# SignalRouting.net
KiCad netlist of a schematic drawn in Altium Designer
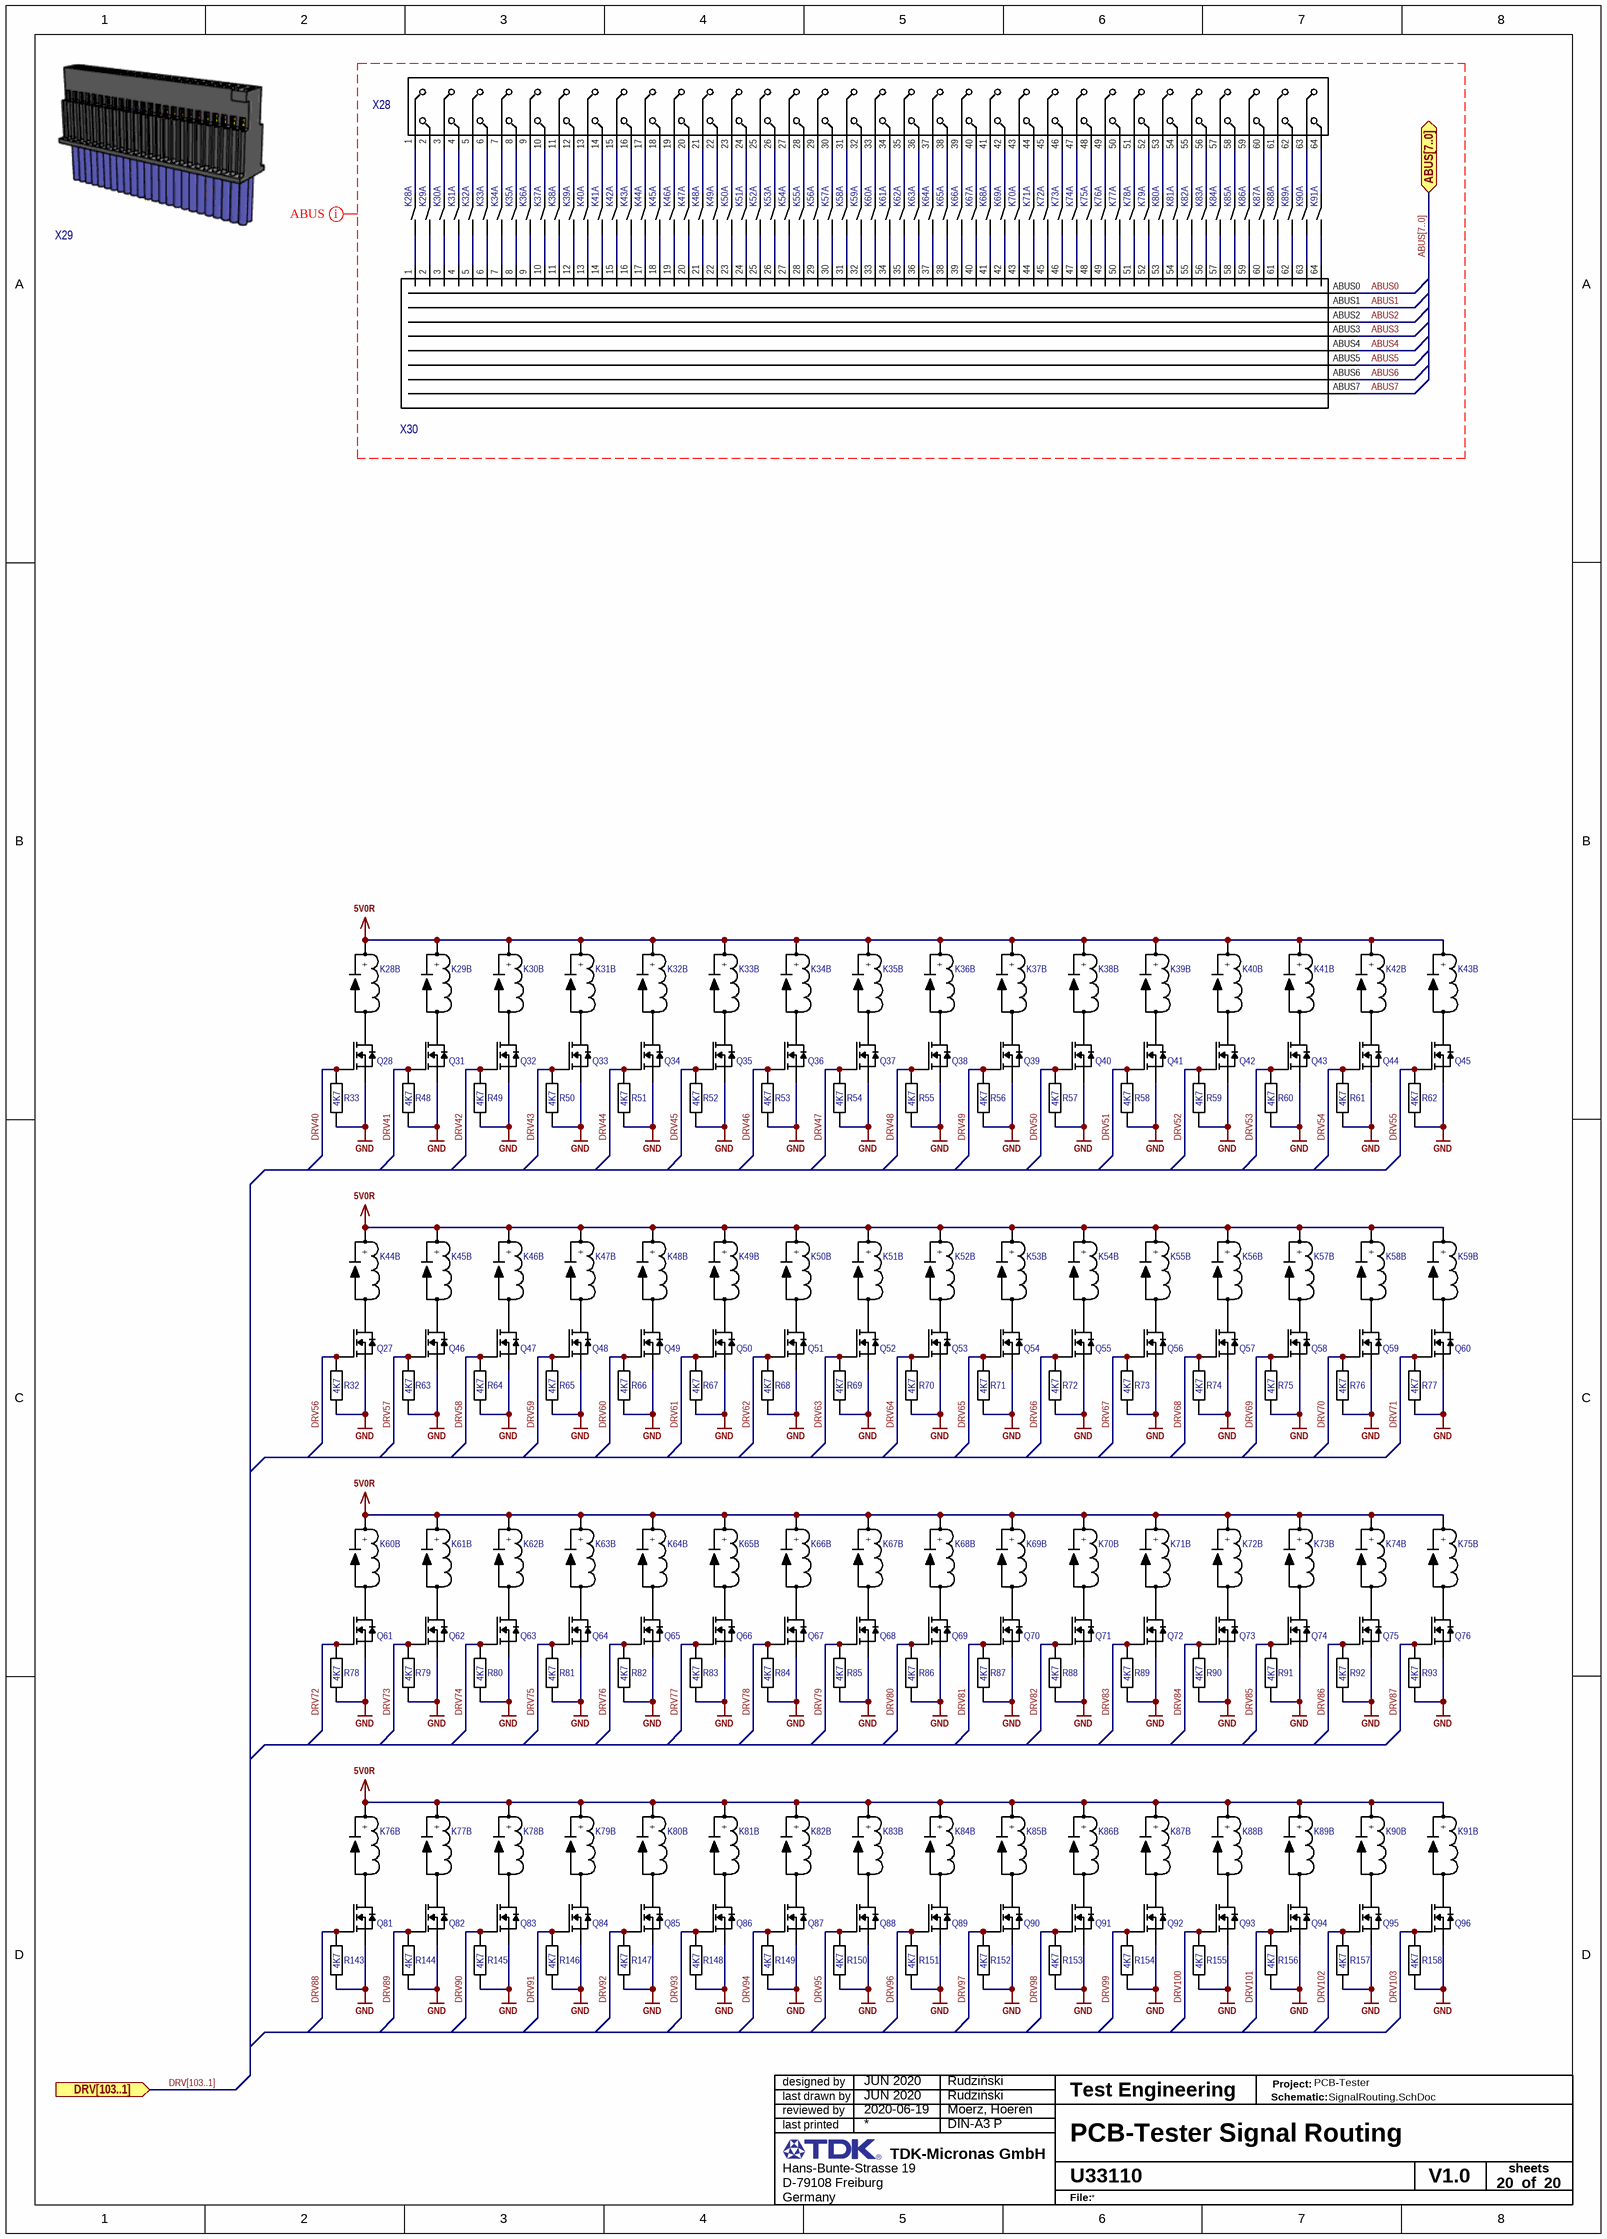
[diagram p0: SignalRouting.SchDoc]

(export (version "E")
  (design (tool "Eeschema 10.0.6"))
  (components
    (comp (ref "K28")
      (value "K")
      (footprint "118-1A")
      (description "5V Signal Relais, Normal Open")
      (fields
        (field (name "02. DISTRIBUTOR PART NUMBER") "118-1-A-5/2D")
        (field (name "13. CREATED DATE/NAME") "20.12.17 S. Kaiser")
      )
      (libsource (lib "chickenfood") (part "118-1-A-5/2D"))
    )
    (comp (ref "K29")
      (value "K")
      (footprint "118-1A")
      (description "5V Signal Relais, Normal Open")
      (fields
        (field (name "02. DISTRIBUTOR PART NUMBER") "118-1-A-5/2D")
        (field (name "13. CREATED DATE/NAME") "20.12.17 S. Kaiser")
      )
      (libsource (lib "") (part "118-1-A-5/2D_1"))
    )
    (comp (ref "K30")
      (value "K")
      (footprint "118-1A")
      (description "5V Signal Relais, Normal Open")
      (fields
        (field (name "02. DISTRIBUTOR PART NUMBER") "118-1-A-5/2D")
        (field (name "13. CREATED DATE/NAME") "20.12.17 S. Kaiser")
      )
      (libsource (lib "") (part "118-1-A-5/2D_1"))
    )
    (comp (ref "K31")
      (value "K")
      (footprint "118-1A")
      (description "5V Signal Relais, Normal Open")
      (fields
        (field (name "02. DISTRIBUTOR PART NUMBER") "118-1-A-5/2D")
        (field (name "13. CREATED DATE/NAME") "20.12.17 S. Kaiser")
      )
      (libsource (lib "chickenfood") (part "118-1-A-5/2D"))
    )
    (comp (ref "K32")
      (value "K")
      (footprint "118-1A")
      (description "5V Signal Relais, Normal Open")
      (fields
        (field (name "02. DISTRIBUTOR PART NUMBER") "118-1-A-5/2D")
        (field (name "13. CREATED DATE/NAME") "20.12.17 S. Kaiser")
      )
      (libsource (lib "chickenfood") (part "118-1-A-5/2D"))
    )
    (comp (ref "K33")
      (value "K")
      (footprint "118-1A")
      (description "5V Signal Relais, Normal Open")
      (fields
        (field (name "02. DISTRIBUTOR PART NUMBER") "118-1-A-5/2D")
        (field (name "13. CREATED DATE/NAME") "20.12.17 S. Kaiser")
      )
      (libsource (lib "chickenfood") (part "118-1-A-5/2D"))
    )
    (comp (ref "K34")
      (value "K")
      (footprint "118-1A")
      (description "5V Signal Relais, Normal Open")
      (fields
        (field (name "02. DISTRIBUTOR PART NUMBER") "118-1-A-5/2D")
        (field (name "13. CREATED DATE/NAME") "20.12.17 S. Kaiser")
      )
      (libsource (lib "chickenfood") (part "118-1-A-5/2D"))
    )
    (comp (ref "K35")
      (value "K")
      (footprint "118-1A")
      (description "5V Signal Relais, Normal Open")
      (fields
        (field (name "02. DISTRIBUTOR PART NUMBER") "118-1-A-5/2D")
        (field (name "13. CREATED DATE/NAME") "20.12.17 S. Kaiser")
      )
      (libsource (lib "chickenfood") (part "118-1-A-5/2D"))
    )
    (comp (ref "K36")
      (value "K")
      (footprint "118-1A")
      (description "5V Signal Relais, Normal Open")
      (fields
        (field (name "02. DISTRIBUTOR PART NUMBER") "118-1-A-5/2D")
        (field (name "13. CREATED DATE/NAME") "20.12.17 S. Kaiser")
      )
      (libsource (lib "") (part "118-1-A-5/2D_1"))
    )
    (comp (ref "K37")
      (value "K")
      (footprint "118-1A")
      (description "5V Signal Relais, Normal Open")
      (fields
        (field (name "02. DISTRIBUTOR PART NUMBER") "118-1-A-5/2D")
        (field (name "13. CREATED DATE/NAME") "20.12.17 S. Kaiser")
      )
      (libsource (lib "") (part "118-1-A-5/2D_1"))
    )
    (comp (ref "K38")
      (value "K")
      (footprint "118-1A")
      (description "5V Signal Relais, Normal Open")
      (fields
        (field (name "02. DISTRIBUTOR PART NUMBER") "118-1-A-5/2D")
        (field (name "13. CREATED DATE/NAME") "20.12.17 S. Kaiser")
      )
      (libsource (lib "") (part "118-1-A-5/2D_1"))
    )
    (comp (ref "K39")
      (value "K")
      (footprint "118-1A")
      (description "5V Signal Relais, Normal Open")
      (fields
        (field (name "02. DISTRIBUTOR PART NUMBER") "118-1-A-5/2D")
        (field (name "13. CREATED DATE/NAME") "20.12.17 S. Kaiser")
      )
      (libsource (lib "") (part "118-1-A-5/2D_1"))
    )
    (comp (ref "K40")
      (value "K")
      (footprint "118-1A")
      (description "5V Signal Relais, Normal Open")
      (fields
        (field (name "02. DISTRIBUTOR PART NUMBER") "118-1-A-5/2D")
        (field (name "13. CREATED DATE/NAME") "20.12.17 S. Kaiser")
      )
      (libsource (lib "chickenfood") (part "118-1-A-5/2D"))
    )
    (comp (ref "K41")
      (value "K")
      (footprint "118-1A")
      (description "5V Signal Relais, Normal Open")
      (fields
        (field (name "02. DISTRIBUTOR PART NUMBER") "118-1-A-5/2D")
        (field (name "13. CREATED DATE/NAME") "20.12.17 S. Kaiser")
      )
      (libsource (lib "") (part "118-1-A-5/2D_1"))
    )
    (comp (ref "K42")
      (value "K")
      (footprint "118-1A")
      (description "5V Signal Relais, Normal Open")
      (fields
        (field (name "02. DISTRIBUTOR PART NUMBER") "118-1-A-5/2D")
        (field (name "13. CREATED DATE/NAME") "20.12.17 S. Kaiser")
      )
      (libsource (lib "") (part "118-1-A-5/2D_1"))
    )
    (comp (ref "K43")
      (value "K")
      (footprint "118-1A")
      (description "5V Signal Relais, Normal Open")
      (fields
        (field (name "02. DISTRIBUTOR PART NUMBER") "118-1-A-5/2D")
        (field (name "13. CREATED DATE/NAME") "20.12.17 S. Kaiser")
      )
      (libsource (lib "chickenfood") (part "118-1-A-5/2D"))
    )
    (comp (ref "K44")
      (value "K")
      (footprint "118-1A")
      (description "5V Signal Relais, Normal Open")
      (fields
        (field (name "02. DISTRIBUTOR PART NUMBER") "118-1-A-5/2D")
        (field (name "13. CREATED DATE/NAME") "20.12.17 S. Kaiser")
      )
      (libsource (lib "chickenfood") (part "118-1-A-5/2D"))
    )
    (comp (ref "K45")
      (value "K")
      (footprint "118-1A")
      (description "5V Signal Relais, Normal Open")
      (fields
        (field (name "02. DISTRIBUTOR PART NUMBER") "118-1-A-5/2D")
        (field (name "13. CREATED DATE/NAME") "20.12.17 S. Kaiser")
      )
      (libsource (lib "chickenfood") (part "118-1-A-5/2D"))
    )
    (comp (ref "K46")
      (value "K")
      (footprint "118-1A")
      (description "5V Signal Relais, Normal Open")
      (fields
        (field (name "02. DISTRIBUTOR PART NUMBER") "118-1-A-5/2D")
        (field (name "13. CREATED DATE/NAME") "20.12.17 S. Kaiser")
      )
      (libsource (lib "") (part "118-1-A-5/2D_1"))
    )
    (comp (ref "K47")
      (value "K")
      (footprint "118-1A")
      (description "5V Signal Relais, Normal Open")
      (fields
        (field (name "02. DISTRIBUTOR PART NUMBER") "118-1-A-5/2D")
        (field (name "13. CREATED DATE/NAME") "20.12.17 S. Kaiser")
      )
      (libsource (lib "chickenfood") (part "118-1-A-5/2D"))
    )
    (comp (ref "K48")
      (value "K")
      (footprint "118-1A")
      (description "5V Signal Relais, Normal Open")
      (fields
        (field (name "02. DISTRIBUTOR PART NUMBER") "118-1-A-5/2D")
        (field (name "13. CREATED DATE/NAME") "20.12.17 S. Kaiser")
      )
      (libsource (lib "chickenfood") (part "118-1-A-5/2D"))
    )
    (comp (ref "K49")
      (value "K")
      (footprint "118-1A")
      (description "5V Signal Relais, Normal Open")
      (fields
        (field (name "02. DISTRIBUTOR PART NUMBER") "118-1-A-5/2D")
        (field (name "13. CREATED DATE/NAME") "20.12.17 S. Kaiser")
      )
      (libsource (lib "chickenfood") (part "118-1-A-5/2D"))
    )
    (comp (ref "K50")
      (value "K")
      (footprint "118-1A")
      (description "5V Signal Relais, Normal Open")
      (fields
        (field (name "02. DISTRIBUTOR PART NUMBER") "118-1-A-5/2D")
        (field (name "13. CREATED DATE/NAME") "20.12.17 S. Kaiser")
      )
      (libsource (lib "chickenfood") (part "118-1-A-5/2D"))
    )
    (comp (ref "K51")
      (value "K")
      (footprint "118-1A")
      (description "5V Signal Relais, Normal Open")
      (fields
        (field (name "02. DISTRIBUTOR PART NUMBER") "118-1-A-5/2D")
        (field (name "13. CREATED DATE/NAME") "20.12.17 S. Kaiser")
      )
      (libsource (lib "chickenfood") (part "118-1-A-5/2D"))
    )
    (comp (ref "K52")
      (value "K")
      (footprint "118-1A")
      (description "5V Signal Relais, Normal Open")
      (fields
        (field (name "02. DISTRIBUTOR PART NUMBER") "118-1-A-5/2D")
        (field (name "13. CREATED DATE/NAME") "20.12.17 S. Kaiser")
      )
      (libsource (lib "") (part "118-1-A-5/2D_1"))
    )
    (comp (ref "K53")
      (value "K")
      (footprint "118-1A")
      (description "5V Signal Relais, Normal Open")
      (fields
        (field (name "02. DISTRIBUTOR PART NUMBER") "118-1-A-5/2D")
        (field (name "13. CREATED DATE/NAME") "20.12.17 S. Kaiser")
      )
      (libsource (lib "") (part "118-1-A-5/2D_1"))
    )
    (comp (ref "K54")
      (value "K")
      (footprint "118-1A")
      (description "5V Signal Relais, Normal Open")
      (fields
        (field (name "02. DISTRIBUTOR PART NUMBER") "118-1-A-5/2D")
        (field (name "13. CREATED DATE/NAME") "20.12.17 S. Kaiser")
      )
      (libsource (lib "chickenfood") (part "118-1-A-5/2D"))
    )
    (comp (ref "K55")
      (value "K")
      (footprint "118-1A")
      (description "5V Signal Relais, Normal Open")
      (fields
        (field (name "02. DISTRIBUTOR PART NUMBER") "118-1-A-5/2D")
        (field (name "13. CREATED DATE/NAME") "20.12.17 S. Kaiser")
      )
      (libsource (lib "") (part "118-1-A-5/2D_1"))
    )
    (comp (ref "K56")
      (value "K")
      (footprint "118-1A")
      (description "5V Signal Relais, Normal Open")
      (fields
        (field (name "02. DISTRIBUTOR PART NUMBER") "118-1-A-5/2D")
        (field (name "13. CREATED DATE/NAME") "20.12.17 S. Kaiser")
      )
      (libsource (lib "") (part "118-1-A-5/2D_1"))
    )
    (comp (ref "K57")
      (value "K")
      (footprint "118-1A")
      (description "5V Signal Relais, Normal Open")
      (fields
        (field (name "02. DISTRIBUTOR PART NUMBER") "118-1-A-5/2D")
        (field (name "13. CREATED DATE/NAME") "20.12.17 S. Kaiser")
      )
      (libsource (lib "") (part "118-1-A-5/2D_1"))
    )
    (comp (ref "K58")
      (value "K")
      (footprint "118-1A")
      (description "5V Signal Relais, Normal Open")
      (fields
        (field (name "02. DISTRIBUTOR PART NUMBER") "118-1-A-5/2D")
        (field (name "13. CREATED DATE/NAME") "20.12.17 S. Kaiser")
      )
      (libsource (lib "") (part "118-1-A-5/2D_1"))
    )
    (comp (ref "K59")
      (value "K")
      (footprint "118-1A")
      (description "5V Signal Relais, Normal Open")
      (fields
        (field (name "02. DISTRIBUTOR PART NUMBER") "118-1-A-5/2D")
        (field (name "13. CREATED DATE/NAME") "20.12.17 S. Kaiser")
      )
      (libsource (lib "") (part "118-1-A-5/2D_1"))
    )
    (comp (ref "K60")
      (value "K")
      (footprint "118-1A")
      (description "5V Signal Relais, Normal Open")
      (fields
        (field (name "02. DISTRIBUTOR PART NUMBER") "118-1-A-5/2D")
        (field (name "13. CREATED DATE/NAME") "20.12.17 S. Kaiser")
      )
      (libsource (lib "chickenfood") (part "118-1-A-5/2D"))
    )
    (comp (ref "K61")
      (value "K")
      (footprint "118-1A")
      (description "5V Signal Relais, Normal Open")
      (fields
        (field (name "02. DISTRIBUTOR PART NUMBER") "118-1-A-5/2D")
        (field (name "13. CREATED DATE/NAME") "20.12.17 S. Kaiser")
      )
      (libsource (lib "") (part "118-1-A-5/2D_1"))
    )
    (comp (ref "K62")
      (value "K")
      (footprint "118-1A")
      (description "5V Signal Relais, Normal Open")
      (fields
        (field (name "02. DISTRIBUTOR PART NUMBER") "118-1-A-5/2D")
        (field (name "13. CREATED DATE/NAME") "20.12.17 S. Kaiser")
      )
      (libsource (lib "chickenfood") (part "118-1-A-5/2D"))
    )
    (comp (ref "K63")
      (value "K")
      (footprint "118-1A")
      (description "5V Signal Relais, Normal Open")
      (fields
        (field (name "02. DISTRIBUTOR PART NUMBER") "118-1-A-5/2D")
        (field (name "13. CREATED DATE/NAME") "20.12.17 S. Kaiser")
      )
      (libsource (lib "chickenfood") (part "118-1-A-5/2D"))
    )
    (comp (ref "K64")
      (value "K")
      (footprint "118-1A")
      (description "5V Signal Relais, Normal Open")
      (fields
        (field (name "02. DISTRIBUTOR PART NUMBER") "118-1-A-5/2D")
        (field (name "13. CREATED DATE/NAME") "20.12.17 S. Kaiser")
      )
      (libsource (lib "chickenfood") (part "118-1-A-5/2D"))
    )
    (comp (ref "K65")
      (value "K")
      (footprint "118-1A")
      (description "5V Signal Relais, Normal Open")
      (fields
        (field (name "02. DISTRIBUTOR PART NUMBER") "118-1-A-5/2D")
        (field (name "13. CREATED DATE/NAME") "20.12.17 S. Kaiser")
      )
      (libsource (lib "chickenfood") (part "118-1-A-5/2D"))
    )
    (comp (ref "K66")
      (value "K")
      (footprint "118-1A")
      (description "5V Signal Relais, Normal Open")
      (fields
        (field (name "02. DISTRIBUTOR PART NUMBER") "118-1-A-5/2D")
        (field (name "13. CREATED DATE/NAME") "20.12.17 S. Kaiser")
      )
      (libsource (lib "chickenfood") (part "118-1-A-5/2D"))
    )
    (comp (ref "K67")
      (value "K")
      (footprint "118-1A")
      (description "5V Signal Relais, Normal Open")
      (fields
        (field (name "02. DISTRIBUTOR PART NUMBER") "118-1-A-5/2D")
        (field (name "13. CREATED DATE/NAME") "20.12.17 S. Kaiser")
      )
      (libsource (lib "chickenfood") (part "118-1-A-5/2D"))
    )
    (comp (ref "K68")
      (value "K")
      (footprint "118-1A")
      (description "5V Signal Relais, Normal Open")
      (fields
        (field (name "02. DISTRIBUTOR PART NUMBER") "118-1-A-5/2D")
        (field (name "13. CREATED DATE/NAME") "20.12.17 S. Kaiser")
      )
      (libsource (lib "") (part "118-1-A-5/2D_1"))
    )
    (comp (ref "K69")
      (value "K")
      (footprint "118-1A")
      (description "5V Signal Relais, Normal Open")
      (fields
        (field (name "02. DISTRIBUTOR PART NUMBER") "118-1-A-5/2D")
        (field (name "13. CREATED DATE/NAME") "20.12.17 S. Kaiser")
      )
      (libsource (lib "chickenfood") (part "118-1-A-5/2D"))
    )
    (comp (ref "K70")
      (value "K")
      (footprint "118-1A")
      (description "5V Signal Relais, Normal Open")
      (fields
        (field (name "02. DISTRIBUTOR PART NUMBER") "118-1-A-5/2D")
        (field (name "13. CREATED DATE/NAME") "20.12.17 S. Kaiser")
      )
      (libsource (lib "") (part "118-1-A-5/2D_1"))
    )
    (comp (ref "K71")
      (value "K")
      (footprint "118-1A")
      (description "5V Signal Relais, Normal Open")
      (fields
        (field (name "02. DISTRIBUTOR PART NUMBER") "118-1-A-5/2D")
        (field (name "13. CREATED DATE/NAME") "20.12.17 S. Kaiser")
      )
      (libsource (lib "chickenfood") (part "118-1-A-5/2D"))
    )
    (comp (ref "K72")
      (value "K")
      (footprint "118-1A")
      (description "5V Signal Relais, Normal Open")
      (fields
        (field (name "02. DISTRIBUTOR PART NUMBER") "118-1-A-5/2D")
        (field (name "13. CREATED DATE/NAME") "20.12.17 S. Kaiser")
      )
      (libsource (lib "") (part "118-1-A-5/2D_1"))
    )
    (comp (ref "K73")
      (value "K")
      (footprint "118-1A")
      (description "5V Signal Relais, Normal Open")
      (fields
        (field (name "02. DISTRIBUTOR PART NUMBER") "118-1-A-5/2D")
        (field (name "13. CREATED DATE/NAME") "20.12.17 S. Kaiser")
      )
      (libsource (lib "") (part "118-1-A-5/2D_1"))
    )
    (comp (ref "K74")
      (value "K")
      (footprint "118-1A")
      (description "5V Signal Relais, Normal Open")
      (fields
        (field (name "02. DISTRIBUTOR PART NUMBER") "118-1-A-5/2D")
        (field (name "13. CREATED DATE/NAME") "20.12.17 S. Kaiser")
      )
      (libsource (lib "") (part "118-1-A-5/2D_1"))
    )
    (comp (ref "K75")
      (value "K")
      (footprint "118-1A")
      (description "5V Signal Relais, Normal Open")
      (fields
        (field (name "02. DISTRIBUTOR PART NUMBER") "118-1-A-5/2D")
        (field (name "13. CREATED DATE/NAME") "20.12.17 S. Kaiser")
      )
      (libsource (lib "chickenfood") (part "118-1-A-5/2D"))
    )
    (comp (ref "K76")
      (value "K")
      (footprint "118-1A")
      (description "5V Signal Relais, Normal Open")
      (fields
        (field (name "02. DISTRIBUTOR PART NUMBER") "118-1-A-5/2D")
        (field (name "13. CREATED DATE/NAME") "20.12.17 S. Kaiser")
      )
      (libsource (lib "chickenfood") (part "118-1-A-5/2D"))
    )
    (comp (ref "K77")
      (value "K")
      (footprint "118-1A")
      (description "5V Signal Relais, Normal Open")
      (fields
        (field (name "02. DISTRIBUTOR PART NUMBER") "118-1-A-5/2D")
        (field (name "13. CREATED DATE/NAME") "20.12.17 S. Kaiser")
      )
      (libsource (lib "") (part "118-1-A-5/2D_1"))
    )
    (comp (ref "K78")
      (value "K")
      (footprint "118-1A")
      (description "5V Signal Relais, Normal Open")
      (fields
        (field (name "02. DISTRIBUTOR PART NUMBER") "118-1-A-5/2D")
        (field (name "13. CREATED DATE/NAME") "20.12.17 S. Kaiser")
      )
      (libsource (lib "chickenfood") (part "118-1-A-5/2D"))
    )
    (comp (ref "K79")
      (value "K")
      (footprint "118-1A")
      (description "5V Signal Relais, Normal Open")
      (fields
        (field (name "02. DISTRIBUTOR PART NUMBER") "118-1-A-5/2D")
        (field (name "13. CREATED DATE/NAME") "20.12.17 S. Kaiser")
      )
      (libsource (lib "chickenfood") (part "118-1-A-5/2D"))
    )
    (comp (ref "K80")
      (value "K")
      (footprint "118-1A")
      (description "5V Signal Relais, Normal Open")
      (fields
        (field (name "02. DISTRIBUTOR PART NUMBER") "118-1-A-5/2D")
        (field (name "13. CREATED DATE/NAME") "20.12.17 S. Kaiser")
      )
      (libsource (lib "") (part "118-1-A-5/2D_1"))
    )
    (comp (ref "K81")
      (value "K")
      (footprint "118-1A")
      (description "5V Signal Relais, Normal Open")
      (fields
        (field (name "02. DISTRIBUTOR PART NUMBER") "118-1-A-5/2D")
        (field (name "13. CREATED DATE/NAME") "20.12.17 S. Kaiser")
      )
      (libsource (lib "chickenfood") (part "118-1-A-5/2D"))
    )
    (comp (ref "K82")
      (value "K")
      (footprint "118-1A")
      (description "5V Signal Relais, Normal Open")
      (fields
        (field (name "02. DISTRIBUTOR PART NUMBER") "118-1-A-5/2D")
        (field (name "13. CREATED DATE/NAME") "20.12.17 S. Kaiser")
      )
      (libsource (lib "") (part "118-1-A-5/2D_1"))
    )
    (comp (ref "K83")
      (value "K")
      (footprint "118-1A")
      (description "5V Signal Relais, Normal Open")
      (fields
        (field (name "02. DISTRIBUTOR PART NUMBER") "118-1-A-5/2D")
        (field (name "13. CREATED DATE/NAME") "20.12.17 S. Kaiser")
      )
      (libsource (lib "chickenfood") (part "118-1-A-5/2D"))
    )
    (comp (ref "K84")
      (value "K")
      (footprint "118-1A")
      (description "5V Signal Relais, Normal Open")
      (fields
        (field (name "02. DISTRIBUTOR PART NUMBER") "118-1-A-5/2D")
        (field (name "13. CREATED DATE/NAME") "20.12.17 S. Kaiser")
      )
      (libsource (lib "chickenfood") (part "118-1-A-5/2D"))
    )
    (comp (ref "K85")
      (value "K")
      (footprint "118-1A")
      (description "5V Signal Relais, Normal Open")
      (fields
        (field (name "02. DISTRIBUTOR PART NUMBER") "118-1-A-5/2D")
        (field (name "13. CREATED DATE/NAME") "20.12.17 S. Kaiser")
      )
      (libsource (lib "chickenfood") (part "118-1-A-5/2D"))
    )
    (comp (ref "K86")
      (value "K")
      (footprint "118-1A")
      (description "5V Signal Relais, Normal Open")
      (fields
        (field (name "02. DISTRIBUTOR PART NUMBER") "118-1-A-5/2D")
        (field (name "13. CREATED DATE/NAME") "20.12.17 S. Kaiser")
      )
      (libsource (lib "chickenfood") (part "118-1-A-5/2D"))
    )
    (comp (ref "K87")
      (value "K")
      (footprint "118-1A")
      (description "5V Signal Relais, Normal Open")
      (fields
        (field (name "02. DISTRIBUTOR PART NUMBER") "118-1-A-5/2D")
        (field (name "13. CREATED DATE/NAME") "20.12.17 S. Kaiser")
      )
      (libsource (lib "chickenfood") (part "118-1-A-5/2D"))
    )
    (comp (ref "K88")
      (value "K")
      (footprint "118-1A")
      (description "5V Signal Relais, Normal Open")
      (fields
        (field (name "02. DISTRIBUTOR PART NUMBER") "118-1-A-5/2D")
        (field (name "13. CREATED DATE/NAME") "20.12.17 S. Kaiser")
      )
      (libsource (lib "chickenfood") (part "118-1-A-5/2D"))
    )
    (comp (ref "K89")
      (value "K")
      (footprint "118-1A")
      (description "5V Signal Relais, Normal Open")
      (fields
        (field (name "02. DISTRIBUTOR PART NUMBER") "118-1-A-5/2D")
        (field (name "13. CREATED DATE/NAME") "20.12.17 S. Kaiser")
      )
      (libsource (lib "") (part "118-1-A-5/2D_1"))
    )
    (comp (ref "K90")
      (value "K")
      (footprint "118-1A")
      (description "5V Signal Relais, Normal Open")
      (fields
        (field (name "02. DISTRIBUTOR PART NUMBER") "118-1-A-5/2D")
        (field (name "13. CREATED DATE/NAME") "20.12.17 S. Kaiser")
      )
      (libsource (lib "") (part "118-1-A-5/2D_1"))
    )
    (comp (ref "K91")
      (value "K")
      (footprint "118-1A")
      (description "5V Signal Relais, Normal Open")
      (fields
        (field (name "02. DISTRIBUTOR PART NUMBER") "118-1-A-5/2D")
        (field (name "13. CREATED DATE/NAME") "20.12.17 S. Kaiser")
      )
      (libsource (lib "") (part "118-1-A-5/2D_1"))
    )
    (comp (ref "Q27")
      (value "Q")
      (footprint "SOT23-3")
      (description "MOSFET N-CH 25V 680MA SOT-23")
      (fields
        (field (name "02. DISTRIBUTOR PART NUMBER") "FDV303NDKR-ND")
        (field (name "07. MANUFACTURER  PART NUMBER") "FDV303N")
        (field (name "13. CREATED DATE/NAME") "AUG 2018 / Hören")
      )
      (libsource (lib "SCT8-Board1") (part "FDV303N"))
    )
    (comp (ref "Q28")
      (value "Q")
      (footprint "SOT23-3")
      (description "MOSFET N-CH 25V 680MA SOT-23")
      (fields
        (field (name "02. DISTRIBUTOR PART NUMBER") "FDV303NDKR-ND")
        (field (name "07. MANUFACTURER  PART NUMBER") "FDV303N")
        (field (name "13. CREATED DATE/NAME") "AUG 2018 / Hören")
      )
      (libsource (lib "SCT8-Board1") (part "FDV303N"))
    )
    (comp (ref "Q31")
      (value "Q")
      (footprint "SOT23-3")
      (description "MOSFET N-CH 25V 680MA SOT-23")
      (fields
        (field (name "02. DISTRIBUTOR PART NUMBER") "FDV303NDKR-ND")
        (field (name "07. MANUFACTURER  PART NUMBER") "FDV303N")
        (field (name "13. CREATED DATE/NAME") "AUG 2018 / Hören")
      )
      (libsource (lib "SCT8-Board1") (part "FDV303N"))
    )
    (comp (ref "Q32")
      (value "Q")
      (footprint "SOT23-3")
      (description "MOSFET N-CH 25V 680MA SOT-23")
      (fields
        (field (name "02. DISTRIBUTOR PART NUMBER") "FDV303NDKR-ND")
        (field (name "07. MANUFACTURER  PART NUMBER") "FDV303N")
        (field (name "13. CREATED DATE/NAME") "AUG 2018 / Hören")
      )
      (libsource (lib "SCT8-Board1") (part "FDV303N"))
    )
    (comp (ref "Q33")
      (value "Q")
      (footprint "SOT23-3")
      (description "MOSFET N-CH 25V 680MA SOT-23")
      (fields
        (field (name "02. DISTRIBUTOR PART NUMBER") "FDV303NDKR-ND")
        (field (name "07. MANUFACTURER  PART NUMBER") "FDV303N")
        (field (name "13. CREATED DATE/NAME") "AUG 2018 / Hören")
      )
      (libsource (lib "SCT8-Board1") (part "FDV303N"))
    )
    (comp (ref "Q34")
      (value "Q")
      (footprint "SOT23-3")
      (description "MOSFET N-CH 25V 680MA SOT-23")
      (fields
        (field (name "02. DISTRIBUTOR PART NUMBER") "FDV303NDKR-ND")
        (field (name "07. MANUFACTURER  PART NUMBER") "FDV303N")
        (field (name "13. CREATED DATE/NAME") "AUG 2018 / Hören")
      )
      (libsource (lib "SCT8-Board1") (part "FDV303N"))
    )
    (comp (ref "Q35")
      (value "Q")
      (footprint "SOT23-3")
      (description "MOSFET N-CH 25V 680MA SOT-23")
      (fields
        (field (name "02. DISTRIBUTOR PART NUMBER") "FDV303NDKR-ND")
        (field (name "07. MANUFACTURER  PART NUMBER") "FDV303N")
        (field (name "13. CREATED DATE/NAME") "AUG 2018 / Hören")
      )
      (libsource (lib "SCT8-Board1") (part "FDV303N"))
    )
    (comp (ref "Q36")
      (value "Q")
      (footprint "SOT23-3")
      (description "MOSFET N-CH 25V 680MA SOT-23")
      (fields
        (field (name "02. DISTRIBUTOR PART NUMBER") "FDV303NDKR-ND")
        (field (name "07. MANUFACTURER  PART NUMBER") "FDV303N")
        (field (name "13. CREATED DATE/NAME") "AUG 2018 / Hören")
      )
      (libsource (lib "SCT8-Board1") (part "FDV303N"))
    )
    (comp (ref "Q37")
      (value "Q")
      (footprint "SOT23-3")
      (description "MOSFET N-CH 25V 680MA SOT-23")
      (fields
        (field (name "02. DISTRIBUTOR PART NUMBER") "FDV303NDKR-ND")
        (field (name "07. MANUFACTURER  PART NUMBER") "FDV303N")
        (field (name "13. CREATED DATE/NAME") "AUG 2018 / Hören")
      )
      (libsource (lib "SCT8-Board1") (part "FDV303N"))
    )
    (comp (ref "Q38")
      (value "Q")
      (footprint "SOT23-3")
      (description "MOSFET N-CH 25V 680MA SOT-23")
      (fields
        (field (name "02. DISTRIBUTOR PART NUMBER") "FDV303NDKR-ND")
        (field (name "07. MANUFACTURER  PART NUMBER") "FDV303N")
        (field (name "13. CREATED DATE/NAME") "AUG 2018 / Hören")
      )
      (libsource (lib "SCT8-Board1") (part "FDV303N"))
    )
    (comp (ref "Q39")
      (value "Q")
      (footprint "SOT23-3")
      (description "MOSFET N-CH 25V 680MA SOT-23")
      (fields
        (field (name "02. DISTRIBUTOR PART NUMBER") "FDV303NDKR-ND")
        (field (name "07. MANUFACTURER  PART NUMBER") "FDV303N")
        (field (name "13. CREATED DATE/NAME") "AUG 2018 / Hören")
      )
      (libsource (lib "SCT8-Board1") (part "FDV303N"))
    )
    (comp (ref "Q40")
      (value "Q")
      (footprint "SOT23-3")
      (description "MOSFET N-CH 25V 680MA SOT-23")
      (fields
        (field (name "02. DISTRIBUTOR PART NUMBER") "FDV303NDKR-ND")
        (field (name "07. MANUFACTURER  PART NUMBER") "FDV303N")
        (field (name "13. CREATED DATE/NAME") "AUG 2018 / Hören")
      )
      (libsource (lib "SCT8-Board1") (part "FDV303N"))
    )
    (comp (ref "Q41")
      (value "Q")
      (footprint "SOT23-3")
      (description "MOSFET N-CH 25V 680MA SOT-23")
      (fields
        (field (name "02. DISTRIBUTOR PART NUMBER") "FDV303NDKR-ND")
        (field (name "07. MANUFACTURER  PART NUMBER") "FDV303N")
        (field (name "13. CREATED DATE/NAME") "AUG 2018 / Hören")
      )
      (libsource (lib "SCT8-Board1") (part "FDV303N"))
    )
    (comp (ref "Q42")
      (value "Q")
      (footprint "SOT23-3")
      (description "MOSFET N-CH 25V 680MA SOT-23")
      (fields
        (field (name "02. DISTRIBUTOR PART NUMBER") "FDV303NDKR-ND")
        (field (name "07. MANUFACTURER  PART NUMBER") "FDV303N")
        (field (name "13. CREATED DATE/NAME") "AUG 2018 / Hören")
      )
      (libsource (lib "SCT8-Board1") (part "FDV303N"))
    )
    (comp (ref "Q43")
      (value "Q")
      (footprint "SOT23-3")
      (description "MOSFET N-CH 25V 680MA SOT-23")
      (fields
        (field (name "02. DISTRIBUTOR PART NUMBER") "FDV303NDKR-ND")
        (field (name "07. MANUFACTURER  PART NUMBER") "FDV303N")
        (field (name "13. CREATED DATE/NAME") "AUG 2018 / Hören")
      )
      (libsource (lib "SCT8-Board1") (part "FDV303N"))
    )
    (comp (ref "Q44")
      (value "Q")
      (footprint "SOT23-3")
      (description "MOSFET N-CH 25V 680MA SOT-23")
      (fields
        (field (name "02. DISTRIBUTOR PART NUMBER") "FDV303NDKR-ND")
        (field (name "07. MANUFACTURER  PART NUMBER") "FDV303N")
        (field (name "13. CREATED DATE/NAME") "AUG 2018 / Hören")
      )
      (libsource (lib "SCT8-Board1") (part "FDV303N"))
    )
    (comp (ref "Q45")
      (value "Q")
      (footprint "SOT23-3")
      (description "MOSFET N-CH 25V 680MA SOT-23")
      (fields
        (field (name "02. DISTRIBUTOR PART NUMBER") "FDV303NDKR-ND")
        (field (name "07. MANUFACTURER  PART NUMBER") "FDV303N")
        (field (name "13. CREATED DATE/NAME") "AUG 2018 / Hören")
      )
      (libsource (lib "SCT8-Board1") (part "FDV303N"))
    )
    (comp (ref "Q46")
      (value "Q")
      (footprint "SOT23-3")
      (description "MOSFET N-CH 25V 680MA SOT-23")
      (fields
        (field (name "02. DISTRIBUTOR PART NUMBER") "FDV303NDKR-ND")
        (field (name "07. MANUFACTURER  PART NUMBER") "FDV303N")
        (field (name "13. CREATED DATE/NAME") "AUG 2018 / Hören")
      )
      (libsource (lib "SCT8-Board1") (part "FDV303N"))
    )
    (comp (ref "Q47")
      (value "Q")
      (footprint "SOT23-3")
      (description "MOSFET N-CH 25V 680MA SOT-23")
      (fields
        (field (name "02. DISTRIBUTOR PART NUMBER") "FDV303NDKR-ND")
        (field (name "07. MANUFACTURER  PART NUMBER") "FDV303N")
        (field (name "13. CREATED DATE/NAME") "AUG 2018 / Hören")
      )
      (libsource (lib "SCT8-Board1") (part "FDV303N"))
    )
    (comp (ref "Q48")
      (value "Q")
      (footprint "SOT23-3")
      (description "MOSFET N-CH 25V 680MA SOT-23")
      (fields
        (field (name "02. DISTRIBUTOR PART NUMBER") "FDV303NDKR-ND")
        (field (name "07. MANUFACTURER  PART NUMBER") "FDV303N")
        (field (name "13. CREATED DATE/NAME") "AUG 2018 / Hören")
      )
      (libsource (lib "SCT8-Board1") (part "FDV303N"))
    )
    (comp (ref "Q49")
      (value "Q")
      (footprint "SOT23-3")
      (description "MOSFET N-CH 25V 680MA SOT-23")
      (fields
        (field (name "02. DISTRIBUTOR PART NUMBER") "FDV303NDKR-ND")
        (field (name "07. MANUFACTURER  PART NUMBER") "FDV303N")
        (field (name "13. CREATED DATE/NAME") "AUG 2018 / Hören")
      )
      (libsource (lib "SCT8-Board1") (part "FDV303N"))
    )
    (comp (ref "Q50")
      (value "Q")
      (footprint "SOT23-3")
      (description "MOSFET N-CH 25V 680MA SOT-23")
      (fields
        (field (name "02. DISTRIBUTOR PART NUMBER") "FDV303NDKR-ND")
        (field (name "07. MANUFACTURER  PART NUMBER") "FDV303N")
        (field (name "13. CREATED DATE/NAME") "AUG 2018 / Hören")
      )
      (libsource (lib "SCT8-Board1") (part "FDV303N"))
    )
    (comp (ref "Q51")
      (value "Q")
      (footprint "SOT23-3")
      (description "MOSFET N-CH 25V 680MA SOT-23")
      (fields
        (field (name "02. DISTRIBUTOR PART NUMBER") "FDV303NDKR-ND")
        (field (name "07. MANUFACTURER  PART NUMBER") "FDV303N")
        (field (name "13. CREATED DATE/NAME") "AUG 2018 / Hören")
      )
      (libsource (lib "SCT8-Board1") (part "FDV303N"))
    )
    (comp (ref "Q52")
      (value "Q")
      (footprint "SOT23-3")
      (description "MOSFET N-CH 25V 680MA SOT-23")
      (fields
        (field (name "02. DISTRIBUTOR PART NUMBER") "FDV303NDKR-ND")
        (field (name "07. MANUFACTURER  PART NUMBER") "FDV303N")
        (field (name "13. CREATED DATE/NAME") "AUG 2018 / Hören")
      )
      (libsource (lib "SCT8-Board1") (part "FDV303N"))
    )
    (comp (ref "Q53")
      (value "Q")
      (footprint "SOT23-3")
      (description "MOSFET N-CH 25V 680MA SOT-23")
      (fields
        (field (name "02. DISTRIBUTOR PART NUMBER") "FDV303NDKR-ND")
        (field (name "07. MANUFACTURER  PART NUMBER") "FDV303N")
        (field (name "13. CREATED DATE/NAME") "AUG 2018 / Hören")
      )
      (libsource (lib "SCT8-Board1") (part "FDV303N"))
    )
    (comp (ref "Q54")
      (value "Q")
      (footprint "SOT23-3")
      (description "MOSFET N-CH 25V 680MA SOT-23")
      (fields
        (field (name "02. DISTRIBUTOR PART NUMBER") "FDV303NDKR-ND")
        (field (name "07. MANUFACTURER  PART NUMBER") "FDV303N")
        (field (name "13. CREATED DATE/NAME") "AUG 2018 / Hören")
      )
      (libsource (lib "SCT8-Board1") (part "FDV303N"))
    )
    (comp (ref "Q55")
      (value "Q")
      (footprint "SOT23-3")
      (description "MOSFET N-CH 25V 680MA SOT-23")
      (fields
        (field (name "02. DISTRIBUTOR PART NUMBER") "FDV303NDKR-ND")
        (field (name "07. MANUFACTURER  PART NUMBER") "FDV303N")
        (field (name "13. CREATED DATE/NAME") "AUG 2018 / Hören")
      )
      (libsource (lib "SCT8-Board1") (part "FDV303N"))
    )
    (comp (ref "Q56")
      (value "Q")
      (footprint "SOT23-3")
      (description "MOSFET N-CH 25V 680MA SOT-23")
      (fields
        (field (name "02. DISTRIBUTOR PART NUMBER") "FDV303NDKR-ND")
        (field (name "07. MANUFACTURER  PART NUMBER") "FDV303N")
        (field (name "13. CREATED DATE/NAME") "AUG 2018 / Hören")
      )
      (libsource (lib "SCT8-Board1") (part "FDV303N"))
    )
    (comp (ref "Q57")
      (value "Q")
      (footprint "SOT23-3")
      (description "MOSFET N-CH 25V 680MA SOT-23")
      (fields
        (field (name "02. DISTRIBUTOR PART NUMBER") "FDV303NDKR-ND")
        (field (name "07. MANUFACTURER  PART NUMBER") "FDV303N")
        (field (name "13. CREATED DATE/NAME") "AUG 2018 / Hören")
      )
      (libsource (lib "SCT8-Board1") (part "FDV303N"))
    )
    (comp (ref "Q58")
      (value "Q")
      (footprint "SOT23-3")
      (description "MOSFET N-CH 25V 680MA SOT-23")
      (fields
        (field (name "02. DISTRIBUTOR PART NUMBER") "FDV303NDKR-ND")
        (field (name "07. MANUFACTURER  PART NUMBER") "FDV303N")
        (field (name "13. CREATED DATE/NAME") "AUG 2018 / Hören")
      )
      (libsource (lib "SCT8-Board1") (part "FDV303N"))
    )
    (comp (ref "Q59")
      (value "Q")
      (footprint "SOT23-3")
      (description "MOSFET N-CH 25V 680MA SOT-23")
      (fields
        (field (name "02. DISTRIBUTOR PART NUMBER") "FDV303NDKR-ND")
        (field (name "07. MANUFACTURER  PART NUMBER") "FDV303N")
        (field (name "13. CREATED DATE/NAME") "AUG 2018 / Hören")
      )
      (libsource (lib "SCT8-Board1") (part "FDV303N"))
    )
    (comp (ref "Q60")
      (value "Q")
      (footprint "SOT23-3")
      (description "MOSFET N-CH 25V 680MA SOT-23")
      (fields
        (field (name "02. DISTRIBUTOR PART NUMBER") "FDV303NDKR-ND")
        (field (name "07. MANUFACTURER  PART NUMBER") "FDV303N")
        (field (name "13. CREATED DATE/NAME") "AUG 2018 / Hören")
      )
      (libsource (lib "SCT8-Board1") (part "FDV303N"))
    )
    (comp (ref "Q61")
      (value "Q")
      (footprint "SOT23-3")
      (description "MOSFET N-CH 25V 680MA SOT-23")
      (fields
        (field (name "02. DISTRIBUTOR PART NUMBER") "FDV303NDKR-ND")
        (field (name "07. MANUFACTURER  PART NUMBER") "FDV303N")
        (field (name "13. CREATED DATE/NAME") "AUG 2018 / Hören")
      )
      (libsource (lib "SCT8-Board1") (part "FDV303N"))
    )
    (comp (ref "Q62")
      (value "Q")
      (footprint "SOT23-3")
      (description "MOSFET N-CH 25V 680MA SOT-23")
      (fields
        (field (name "02. DISTRIBUTOR PART NUMBER") "FDV303NDKR-ND")
        (field (name "07. MANUFACTURER  PART NUMBER") "FDV303N")
        (field (name "13. CREATED DATE/NAME") "AUG 2018 / Hören")
      )
      (libsource (lib "SCT8-Board1") (part "FDV303N"))
    )
    (comp (ref "Q63")
      (value "Q")
      (footprint "SOT23-3")
      (description "MOSFET N-CH 25V 680MA SOT-23")
      (fields
        (field (name "02. DISTRIBUTOR PART NUMBER") "FDV303NDKR-ND")
        (field (name "07. MANUFACTURER  PART NUMBER") "FDV303N")
        (field (name "13. CREATED DATE/NAME") "AUG 2018 / Hören")
      )
      (libsource (lib "SCT8-Board1") (part "FDV303N"))
    )
    (comp (ref "Q64")
      (value "Q")
      (footprint "SOT23-3")
      (description "MOSFET N-CH 25V 680MA SOT-23")
      (fields
        (field (name "02. DISTRIBUTOR PART NUMBER") "FDV303NDKR-ND")
        (field (name "07. MANUFACTURER  PART NUMBER") "FDV303N")
        (field (name "13. CREATED DATE/NAME") "AUG 2018 / Hören")
      )
      (libsource (lib "SCT8-Board1") (part "FDV303N"))
    )
    (comp (ref "Q65")
      (value "Q")
      (footprint "SOT23-3")
      (description "MOSFET N-CH 25V 680MA SOT-23")
      (fields
        (field (name "02. DISTRIBUTOR PART NUMBER") "FDV303NDKR-ND")
        (field (name "07. MANUFACTURER  PART NUMBER") "FDV303N")
        (field (name "13. CREATED DATE/NAME") "AUG 2018 / Hören")
      )
      (libsource (lib "SCT8-Board1") (part "FDV303N"))
    )
    (comp (ref "Q66")
      (value "Q")
      (footprint "SOT23-3")
      (description "MOSFET N-CH 25V 680MA SOT-23")
      (fields
        (field (name "02. DISTRIBUTOR PART NUMBER") "FDV303NDKR-ND")
        (field (name "07. MANUFACTURER  PART NUMBER") "FDV303N")
        (field (name "13. CREATED DATE/NAME") "AUG 2018 / Hören")
      )
      (libsource (lib "SCT8-Board1") (part "FDV303N"))
    )
    (comp (ref "Q67")
      (value "Q")
      (footprint "SOT23-3")
      (description "MOSFET N-CH 25V 680MA SOT-23")
      (fields
        (field (name "02. DISTRIBUTOR PART NUMBER") "FDV303NDKR-ND")
        (field (name "07. MANUFACTURER  PART NUMBER") "FDV303N")
        (field (name "13. CREATED DATE/NAME") "AUG 2018 / Hören")
      )
      (libsource (lib "SCT8-Board1") (part "FDV303N"))
    )
    (comp (ref "Q68")
      (value "Q")
      (footprint "SOT23-3")
      (description "MOSFET N-CH 25V 680MA SOT-23")
      (fields
        (field (name "02. DISTRIBUTOR PART NUMBER") "FDV303NDKR-ND")
        (field (name "07. MANUFACTURER  PART NUMBER") "FDV303N")
        (field (name "13. CREATED DATE/NAME") "AUG 2018 / Hören")
      )
      (libsource (lib "SCT8-Board1") (part "FDV303N"))
    )
    (comp (ref "Q69")
      (value "Q")
      (footprint "SOT23-3")
      (description "MOSFET N-CH 25V 680MA SOT-23")
      (fields
        (field (name "02. DISTRIBUTOR PART NUMBER") "FDV303NDKR-ND")
        (field (name "07. MANUFACTURER  PART NUMBER") "FDV303N")
        (field (name "13. CREATED DATE/NAME") "AUG 2018 / Hören")
      )
      (libsource (lib "SCT8-Board1") (part "FDV303N"))
    )
    (comp (ref "Q70")
      (value "Q")
      (footprint "SOT23-3")
      (description "MOSFET N-CH 25V 680MA SOT-23")
      (fields
        (field (name "02. DISTRIBUTOR PART NUMBER") "FDV303NDKR-ND")
        (field (name "07. MANUFACTURER  PART NUMBER") "FDV303N")
        (field (name "13. CREATED DATE/NAME") "AUG 2018 / Hören")
      )
      (libsource (lib "SCT8-Board1") (part "FDV303N"))
    )
    (comp (ref "Q71")
      (value "Q")
      (footprint "SOT23-3")
      (description "MOSFET N-CH 25V 680MA SOT-23")
      (fields
        (field (name "02. DISTRIBUTOR PART NUMBER") "FDV303NDKR-ND")
        (field (name "07. MANUFACTURER  PART NUMBER") "FDV303N")
        (field (name "13. CREATED DATE/NAME") "AUG 2018 / Hören")
      )
      (libsource (lib "SCT8-Board1") (part "FDV303N"))
    )
    (comp (ref "Q72")
      (value "Q")
      (footprint "SOT23-3")
      (description "MOSFET N-CH 25V 680MA SOT-23")
      (fields
        (field (name "02. DISTRIBUTOR PART NUMBER") "FDV303NDKR-ND")
        (field (name "07. MANUFACTURER  PART NUMBER") "FDV303N")
        (field (name "13. CREATED DATE/NAME") "AUG 2018 / Hören")
      )
      (libsource (lib "SCT8-Board1") (part "FDV303N"))
    )
    (comp (ref "Q73")
      (value "Q")
      (footprint "SOT23-3")
      (description "MOSFET N-CH 25V 680MA SOT-23")
      (fields
        (field (name "02. DISTRIBUTOR PART NUMBER") "FDV303NDKR-ND")
        (field (name "07. MANUFACTURER  PART NUMBER") "FDV303N")
        (field (name "13. CREATED DATE/NAME") "AUG 2018 / Hören")
      )
      (libsource (lib "SCT8-Board1") (part "FDV303N"))
    )
    (comp (ref "Q74")
      (value "Q")
      (footprint "SOT23-3")
      (description "MOSFET N-CH 25V 680MA SOT-23")
      (fields
        (field (name "02. DISTRIBUTOR PART NUMBER") "FDV303NDKR-ND")
        (field (name "07. MANUFACTURER  PART NUMBER") "FDV303N")
        (field (name "13. CREATED DATE/NAME") "AUG 2018 / Hören")
      )
      (libsource (lib "SCT8-Board1") (part "FDV303N"))
    )
    (comp (ref "Q75")
      (value "Q")
      (footprint "SOT23-3")
      (description "MOSFET N-CH 25V 680MA SOT-23")
      (fields
        (field (name "02. DISTRIBUTOR PART NUMBER") "FDV303NDKR-ND")
        (field (name "07. MANUFACTURER  PART NUMBER") "FDV303N")
        (field (name "13. CREATED DATE/NAME") "AUG 2018 / Hören")
      )
      (libsource (lib "SCT8-Board1") (part "FDV303N"))
    )
    (comp (ref "Q76")
      (value "Q")
      (footprint "SOT23-3")
      (description "MOSFET N-CH 25V 680MA SOT-23")
      (fields
        (field (name "02. DISTRIBUTOR PART NUMBER") "FDV303NDKR-ND")
        (field (name "07. MANUFACTURER  PART NUMBER") "FDV303N")
        (field (name "13. CREATED DATE/NAME") "AUG 2018 / Hören")
      )
      (libsource (lib "SCT8-Board1") (part "FDV303N"))
    )
    (comp (ref "Q81")
      (value "Q")
      (footprint "SOT23-3")
      (description "MOSFET N-CH 25V 680MA SOT-23")
      (fields
        (field (name "02. DISTRIBUTOR PART NUMBER") "FDV303NDKR-ND")
        (field (name "07. MANUFACTURER  PART NUMBER") "FDV303N")
        (field (name "13. CREATED DATE/NAME") "AUG 2018 / Hören")
      )
      (libsource (lib "SCT8-Board1") (part "FDV303N"))
    )
    (comp (ref "Q82")
      (value "Q")
      (footprint "SOT23-3")
      (description "MOSFET N-CH 25V 680MA SOT-23")
      (fields
        (field (name "02. DISTRIBUTOR PART NUMBER") "FDV303NDKR-ND")
        (field (name "07. MANUFACTURER  PART NUMBER") "FDV303N")
        (field (name "13. CREATED DATE/NAME") "AUG 2018 / Hören")
      )
      (libsource (lib "SCT8-Board1") (part "FDV303N"))
    )
    (comp (ref "Q83")
      (value "Q")
      (footprint "SOT23-3")
      (description "MOSFET N-CH 25V 680MA SOT-23")
      (fields
        (field (name "02. DISTRIBUTOR PART NUMBER") "FDV303NDKR-ND")
        (field (name "07. MANUFACTURER  PART NUMBER") "FDV303N")
        (field (name "13. CREATED DATE/NAME") "AUG 2018 / Hören")
      )
      (libsource (lib "SCT8-Board1") (part "FDV303N"))
    )
    (comp (ref "Q84")
      (value "Q")
      (footprint "SOT23-3")
      (description "MOSFET N-CH 25V 680MA SOT-23")
      (fields
        (field (name "02. DISTRIBUTOR PART NUMBER") "FDV303NDKR-ND")
        (field (name "07. MANUFACTURER  PART NUMBER") "FDV303N")
        (field (name "13. CREATED DATE/NAME") "AUG 2018 / Hören")
      )
      (libsource (lib "SCT8-Board1") (part "FDV303N"))
    )
    (comp (ref "Q85")
      (value "Q")
      (footprint "SOT23-3")
      (description "MOSFET N-CH 25V 680MA SOT-23")
      (fields
        (field (name "02. DISTRIBUTOR PART NUMBER") "FDV303NDKR-ND")
        (field (name "07. MANUFACTURER  PART NUMBER") "FDV303N")
        (field (name "13. CREATED DATE/NAME") "AUG 2018 / Hören")
      )
      (libsource (lib "SCT8-Board1") (part "FDV303N"))
    )
    (comp (ref "Q86")
      (value "Q")
      (footprint "SOT23-3")
      (description "MOSFET N-CH 25V 680MA SOT-23")
      (fields
        (field (name "02. DISTRIBUTOR PART NUMBER") "FDV303NDKR-ND")
        (field (name "07. MANUFACTURER  PART NUMBER") "FDV303N")
        (field (name "13. CREATED DATE/NAME") "AUG 2018 / Hören")
      )
      (libsource (lib "SCT8-Board1") (part "FDV303N"))
    )
    (comp (ref "Q87")
      (value "Q")
      (footprint "SOT23-3")
      (description "MOSFET N-CH 25V 680MA SOT-23")
      (fields
        (field (name "02. DISTRIBUTOR PART NUMBER") "FDV303NDKR-ND")
        (field (name "07. MANUFACTURER  PART NUMBER") "FDV303N")
        (field (name "13. CREATED DATE/NAME") "AUG 2018 / Hören")
      )
      (libsource (lib "SCT8-Board1") (part "FDV303N"))
    )
    (comp (ref "Q88")
      (value "Q")
      (footprint "SOT23-3")
      (description "MOSFET N-CH 25V 680MA SOT-23")
      (fields
        (field (name "02. DISTRIBUTOR PART NUMBER") "FDV303NDKR-ND")
        (field (name "07. MANUFACTURER  PART NUMBER") "FDV303N")
        (field (name "13. CREATED DATE/NAME") "AUG 2018 / Hören")
      )
      (libsource (lib "SCT8-Board1") (part "FDV303N"))
    )
    (comp (ref "Q89")
      (value "Q")
      (footprint "SOT23-3")
      (description "MOSFET N-CH 25V 680MA SOT-23")
      (fields
        (field (name "02. DISTRIBUTOR PART NUMBER") "FDV303NDKR-ND")
        (field (name "07. MANUFACTURER  PART NUMBER") "FDV303N")
        (field (name "13. CREATED DATE/NAME") "AUG 2018 / Hören")
      )
      (libsource (lib "SCT8-Board1") (part "FDV303N"))
    )
    (comp (ref "Q90")
      (value "Q")
      (footprint "SOT23-3")
      (description "MOSFET N-CH 25V 680MA SOT-23")
      (fields
        (field (name "02. DISTRIBUTOR PART NUMBER") "FDV303NDKR-ND")
        (field (name "07. MANUFACTURER  PART NUMBER") "FDV303N")
        (field (name "13. CREATED DATE/NAME") "AUG 2018 / Hören")
      )
      (libsource (lib "SCT8-Board1") (part "FDV303N"))
    )
    (comp (ref "Q91")
      (value "Q")
      (footprint "SOT23-3")
      (description "MOSFET N-CH 25V 680MA SOT-23")
      (fields
        (field (name "02. DISTRIBUTOR PART NUMBER") "FDV303NDKR-ND")
        (field (name "07. MANUFACTURER  PART NUMBER") "FDV303N")
        (field (name "13. CREATED DATE/NAME") "AUG 2018 / Hören")
      )
      (libsource (lib "SCT8-Board1") (part "FDV303N"))
    )
    (comp (ref "Q92")
      (value "Q")
      (footprint "SOT23-3")
      (description "MOSFET N-CH 25V 680MA SOT-23")
      (fields
        (field (name "02. DISTRIBUTOR PART NUMBER") "FDV303NDKR-ND")
        (field (name "07. MANUFACTURER  PART NUMBER") "FDV303N")
        (field (name "13. CREATED DATE/NAME") "AUG 2018 / Hören")
      )
      (libsource (lib "SCT8-Board1") (part "FDV303N"))
    )
    (comp (ref "Q93")
      (value "Q")
      (footprint "SOT23-3")
      (description "MOSFET N-CH 25V 680MA SOT-23")
      (fields
        (field (name "02. DISTRIBUTOR PART NUMBER") "FDV303NDKR-ND")
        (field (name "07. MANUFACTURER  PART NUMBER") "FDV303N")
        (field (name "13. CREATED DATE/NAME") "AUG 2018 / Hören")
      )
      (libsource (lib "SCT8-Board1") (part "FDV303N"))
    )
    (comp (ref "Q94")
      (value "Q")
      (footprint "SOT23-3")
      (description "MOSFET N-CH 25V 680MA SOT-23")
      (fields
        (field (name "02. DISTRIBUTOR PART NUMBER") "FDV303NDKR-ND")
        (field (name "07. MANUFACTURER  PART NUMBER") "FDV303N")
        (field (name "13. CREATED DATE/NAME") "AUG 2018 / Hören")
      )
      (libsource (lib "SCT8-Board1") (part "FDV303N"))
    )
    (comp (ref "Q95")
      (value "Q")
      (footprint "SOT23-3")
      (description "MOSFET N-CH 25V 680MA SOT-23")
      (fields
        (field (name "02. DISTRIBUTOR PART NUMBER") "FDV303NDKR-ND")
        (field (name "07. MANUFACTURER  PART NUMBER") "FDV303N")
        (field (name "13. CREATED DATE/NAME") "AUG 2018 / Hören")
      )
      (libsource (lib "SCT8-Board1") (part "FDV303N"))
    )
    (comp (ref "Q96")
      (value "Q")
      (footprint "SOT23-3")
      (description "MOSFET N-CH 25V 680MA SOT-23")
      (fields
        (field (name "02. DISTRIBUTOR PART NUMBER") "FDV303NDKR-ND")
        (field (name "07. MANUFACTURER  PART NUMBER") "FDV303N")
        (field (name "13. CREATED DATE/NAME") "AUG 2018 / Hören")
      )
      (libsource (lib "SCT8-Board1") (part "FDV303N"))
    )
    (comp (ref "R32")
      (value "4K7")
      (footprint "R0603 Reflow")
      (description "RES SMD 4.7K OHM 1% 1/10W 0603")
      (fields
        (field (name "TOLERANCE") "±1%")
        (field (name "02. DISTRIBUTOR PART NUMBER") "311-4.70KHRCT-ND")
        (field (name "13. CREATED DATE/NAME") "AUG2018/Hören")
      )
      (libsource (lib "chickenfood") (part "R"))
    )
    (comp (ref "R33")
      (value "4K7")
      (footprint "R0603 Reflow")
      (description "RES SMD 4.7K OHM 1% 1/10W 0603")
      (fields
        (field (name "TOLERANCE") "±1%")
        (field (name "02. DISTRIBUTOR PART NUMBER") "311-4.70KHRCT-ND")
        (field (name "13. CREATED DATE/NAME") "AUG2018/Hören")
      )
      (libsource (lib "chickenfood") (part "R"))
    )
    (comp (ref "R48")
      (value "4K7")
      (footprint "R0603 Reflow")
      (description "RES SMD 4.7K OHM 1% 1/10W 0603")
      (fields
        (field (name "TOLERANCE") "±1%")
        (field (name "02. DISTRIBUTOR PART NUMBER") "311-4.70KHRCT-ND")
        (field (name "13. CREATED DATE/NAME") "AUG2018/Hören")
      )
      (libsource (lib "chickenfood") (part "R"))
    )
    (comp (ref "R49")
      (value "4K7")
      (footprint "R0603 Reflow")
      (description "RES SMD 4.7K OHM 1% 1/10W 0603")
      (fields
        (field (name "TOLERANCE") "±1%")
        (field (name "02. DISTRIBUTOR PART NUMBER") "311-4.70KHRCT-ND")
        (field (name "13. CREATED DATE/NAME") "AUG2018/Hören")
      )
      (libsource (lib "chickenfood") (part "R"))
    )
    (comp (ref "R50")
      (value "4K7")
      (footprint "R0603 Reflow")
      (description "RES SMD 4.7K OHM 1% 1/10W 0603")
      (fields
        (field (name "TOLERANCE") "±1%")
        (field (name "02. DISTRIBUTOR PART NUMBER") "311-4.70KHRCT-ND")
        (field (name "13. CREATED DATE/NAME") "AUG2018/Hören")
      )
      (libsource (lib "chickenfood") (part "R"))
    )
    (comp (ref "R51")
      (value "4K7")
      (footprint "R0603 Reflow")
      (description "RES SMD 4.7K OHM 1% 1/10W 0603")
      (fields
        (field (name "TOLERANCE") "±1%")
        (field (name "02. DISTRIBUTOR PART NUMBER") "311-4.70KHRCT-ND")
        (field (name "13. CREATED DATE/NAME") "AUG2018/Hören")
      )
      (libsource (lib "chickenfood") (part "R"))
    )
    (comp (ref "R52")
      (value "4K7")
      (footprint "R0603 Reflow")
      (description "RES SMD 4.7K OHM 1% 1/10W 0603")
      (fields
        (field (name "TOLERANCE") "±1%")
        (field (name "02. DISTRIBUTOR PART NUMBER") "311-4.70KHRCT-ND")
        (field (name "13. CREATED DATE/NAME") "AUG2018/Hören")
      )
      (libsource (lib "chickenfood") (part "R"))
    )
    (comp (ref "R53")
      (value "4K7")
      (footprint "R0603 Reflow")
      (description "RES SMD 4.7K OHM 1% 1/10W 0603")
      (fields
        (field (name "TOLERANCE") "±1%")
        (field (name "02. DISTRIBUTOR PART NUMBER") "311-4.70KHRCT-ND")
        (field (name "13. CREATED DATE/NAME") "AUG2018/Hören")
      )
      (libsource (lib "chickenfood") (part "R"))
    )
    (comp (ref "R54")
      (value "4K7")
      (footprint "R0603 Reflow")
      (description "RES SMD 4.7K OHM 1% 1/10W 0603")
      (fields
        (field (name "TOLERANCE") "±1%")
        (field (name "02. DISTRIBUTOR PART NUMBER") "311-4.70KHRCT-ND")
        (field (name "13. CREATED DATE/NAME") "AUG2018/Hören")
      )
      (libsource (lib "chickenfood") (part "R"))
    )
    (comp (ref "R55")
      (value "4K7")
      (footprint "R0603 Reflow")
      (description "RES SMD 4.7K OHM 1% 1/10W 0603")
      (fields
        (field (name "TOLERANCE") "±1%")
        (field (name "02. DISTRIBUTOR PART NUMBER") "311-4.70KHRCT-ND")
        (field (name "13. CREATED DATE/NAME") "AUG2018/Hören")
      )
      (libsource (lib "chickenfood") (part "R"))
    )
    (comp (ref "R56")
      (value "4K7")
      (footprint "R0603 Reflow")
      (description "RES SMD 4.7K OHM 1% 1/10W 0603")
      (fields
        (field (name "TOLERANCE") "±1%")
        (field (name "02. DISTRIBUTOR PART NUMBER") "311-4.70KHRCT-ND")
        (field (name "13. CREATED DATE/NAME") "AUG2018/Hören")
      )
      (libsource (lib "chickenfood") (part "R"))
    )
    (comp (ref "R57")
      (value "4K7")
      (footprint "R0603 Reflow")
      (description "RES SMD 4.7K OHM 1% 1/10W 0603")
      (fields
        (field (name "TOLERANCE") "±1%")
        (field (name "02. DISTRIBUTOR PART NUMBER") "311-4.70KHRCT-ND")
        (field (name "13. CREATED DATE/NAME") "AUG2018/Hören")
      )
      (libsource (lib "chickenfood") (part "R"))
    )
    (comp (ref "R58")
      (value "4K7")
      (footprint "R0603 Reflow")
      (description "RES SMD 4.7K OHM 1% 1/10W 0603")
      (fields
        (field (name "TOLERANCE") "±1%")
        (field (name "02. DISTRIBUTOR PART NUMBER") "311-4.70KHRCT-ND")
        (field (name "13. CREATED DATE/NAME") "AUG2018/Hören")
      )
      (libsource (lib "chickenfood") (part "R"))
    )
    (comp (ref "R59")
      (value "4K7")
      (footprint "R0603 Reflow")
      (description "RES SMD 4.7K OHM 1% 1/10W 0603")
      (fields
        (field (name "TOLERANCE") "±1%")
        (field (name "02. DISTRIBUTOR PART NUMBER") "311-4.70KHRCT-ND")
        (field (name "13. CREATED DATE/NAME") "AUG2018/Hören")
      )
      (libsource (lib "chickenfood") (part "R"))
    )
    (comp (ref "R60")
      (value "4K7")
      (footprint "R0603 Reflow")
      (description "RES SMD 4.7K OHM 1% 1/10W 0603")
      (fields
        (field (name "TOLERANCE") "±1%")
        (field (name "02. DISTRIBUTOR PART NUMBER") "311-4.70KHRCT-ND")
        (field (name "13. CREATED DATE/NAME") "AUG2018/Hören")
      )
      (libsource (lib "chickenfood") (part "R"))
    )
    (comp (ref "R61")
      (value "4K7")
      (footprint "R0603 Reflow")
      (description "RES SMD 4.7K OHM 1% 1/10W 0603")
      (fields
        (field (name "TOLERANCE") "±1%")
        (field (name "02. DISTRIBUTOR PART NUMBER") "311-4.70KHRCT-ND")
        (field (name "13. CREATED DATE/NAME") "AUG2018/Hören")
      )
      (libsource (lib "chickenfood") (part "R"))
    )
    (comp (ref "R62")
      (value "4K7")
      (footprint "R0603 Reflow")
      (description "RES SMD 4.7K OHM 1% 1/10W 0603")
      (fields
        (field (name "TOLERANCE") "±1%")
        (field (name "02. DISTRIBUTOR PART NUMBER") "311-4.70KHRCT-ND")
        (field (name "13. CREATED DATE/NAME") "AUG2018/Hören")
      )
      (libsource (lib "chickenfood") (part "R"))
    )
    (comp (ref "R63")
      (value "4K7")
      (footprint "R0603 Reflow")
      (description "RES SMD 4.7K OHM 1% 1/10W 0603")
      (fields
        (field (name "TOLERANCE") "±1%")
        (field (name "02. DISTRIBUTOR PART NUMBER") "311-4.70KHRCT-ND")
        (field (name "13. CREATED DATE/NAME") "AUG2018/Hören")
      )
      (libsource (lib "chickenfood") (part "R"))
    )
    (comp (ref "R64")
      (value "4K7")
      (footprint "R0603 Reflow")
      (description "RES SMD 4.7K OHM 1% 1/10W 0603")
      (fields
        (field (name "TOLERANCE") "±1%")
        (field (name "02. DISTRIBUTOR PART NUMBER") "311-4.70KHRCT-ND")
        (field (name "13. CREATED DATE/NAME") "AUG2018/Hören")
      )
      (libsource (lib "chickenfood") (part "R"))
    )
    (comp (ref "R65")
      (value "4K7")
      (footprint "R0603 Reflow")
      (description "RES SMD 4.7K OHM 1% 1/10W 0603")
      (fields
        (field (name "TOLERANCE") "±1%")
        (field (name "02. DISTRIBUTOR PART NUMBER") "311-4.70KHRCT-ND")
        (field (name "13. CREATED DATE/NAME") "AUG2018/Hören")
      )
      (libsource (lib "chickenfood") (part "R"))
    )
    (comp (ref "R66")
      (value "4K7")
      (footprint "R0603 Reflow")
      (description "RES SMD 4.7K OHM 1% 1/10W 0603")
      (fields
        (field (name "TOLERANCE") "±1%")
        (field (name "02. DISTRIBUTOR PART NUMBER") "311-4.70KHRCT-ND")
        (field (name "13. CREATED DATE/NAME") "AUG2018/Hören")
      )
      (libsource (lib "chickenfood") (part "R"))
    )
    (comp (ref "R67")
      (value "4K7")
      (footprint "R0603 Reflow")
      (description "RES SMD 4.7K OHM 1% 1/10W 0603")
      (fields
        (field (name "TOLERANCE") "±1%")
        (field (name "02. DISTRIBUTOR PART NUMBER") "311-4.70KHRCT-ND")
        (field (name "13. CREATED DATE/NAME") "AUG2018/Hören")
      )
      (libsource (lib "chickenfood") (part "R"))
    )
    (comp (ref "R68")
      (value "4K7")
      (footprint "R0603 Reflow")
      (description "RES SMD 4.7K OHM 1% 1/10W 0603")
      (fields
        (field (name "TOLERANCE") "±1%")
        (field (name "02. DISTRIBUTOR PART NUMBER") "311-4.70KHRCT-ND")
        (field (name "13. CREATED DATE/NAME") "AUG2018/Hören")
      )
      (libsource (lib "chickenfood") (part "R"))
    )
    (comp (ref "R69")
      (value "4K7")
      (footprint "R0603 Reflow")
      (description "RES SMD 4.7K OHM 1% 1/10W 0603")
      (fields
        (field (name "TOLERANCE") "±1%")
        (field (name "02. DISTRIBUTOR PART NUMBER") "311-4.70KHRCT-ND")
        (field (name "13. CREATED DATE/NAME") "AUG2018/Hören")
      )
      (libsource (lib "chickenfood") (part "R"))
    )
    (comp (ref "R70")
      (value "4K7")
      (footprint "R0603 Reflow")
      (description "RES SMD 4.7K OHM 1% 1/10W 0603")
      (fields
        (field (name "TOLERANCE") "±1%")
        (field (name "02. DISTRIBUTOR PART NUMBER") "311-4.70KHRCT-ND")
        (field (name "13. CREATED DATE/NAME") "AUG2018/Hören")
      )
      (libsource (lib "chickenfood") (part "R"))
    )
    (comp (ref "R71")
      (value "4K7")
      (footprint "R0603 Reflow")
      (description "RES SMD 4.7K OHM 1% 1/10W 0603")
      (fields
        (field (name "TOLERANCE") "±1%")
        (field (name "02. DISTRIBUTOR PART NUMBER") "311-4.70KHRCT-ND")
        (field (name "13. CREATED DATE/NAME") "AUG2018/Hören")
      )
      (libsource (lib "chickenfood") (part "R"))
    )
    (comp (ref "R72")
      (value "4K7")
      (footprint "R0603 Reflow")
      (description "RES SMD 4.7K OHM 1% 1/10W 0603")
      (fields
        (field (name "TOLERANCE") "±1%")
        (field (name "02. DISTRIBUTOR PART NUMBER") "311-4.70KHRCT-ND")
        (field (name "13. CREATED DATE/NAME") "AUG2018/Hören")
      )
      (libsource (lib "chickenfood") (part "R"))
    )
    (comp (ref "R73")
      (value "4K7")
      (footprint "R0603 Reflow")
      (description "RES SMD 4.7K OHM 1% 1/10W 0603")
      (fields
        (field (name "TOLERANCE") "±1%")
        (field (name "02. DISTRIBUTOR PART NUMBER") "311-4.70KHRCT-ND")
        (field (name "13. CREATED DATE/NAME") "AUG2018/Hören")
      )
      (libsource (lib "chickenfood") (part "R"))
    )
    (comp (ref "R74")
      (value "4K7")
      (footprint "R0603 Reflow")
      (description "RES SMD 4.7K OHM 1% 1/10W 0603")
      (fields
        (field (name "TOLERANCE") "±1%")
        (field (name "02. DISTRIBUTOR PART NUMBER") "311-4.70KHRCT-ND")
        (field (name "13. CREATED DATE/NAME") "AUG2018/Hören")
      )
      (libsource (lib "chickenfood") (part "R"))
    )
    (comp (ref "R75")
      (value "4K7")
      (footprint "R0603 Reflow")
      (description "RES SMD 4.7K OHM 1% 1/10W 0603")
      (fields
        (field (name "TOLERANCE") "±1%")
        (field (name "02. DISTRIBUTOR PART NUMBER") "311-4.70KHRCT-ND")
        (field (name "13. CREATED DATE/NAME") "AUG2018/Hören")
      )
      (libsource (lib "chickenfood") (part "R"))
    )
    (comp (ref "R76")
      (value "4K7")
      (footprint "R0603 Reflow")
      (description "RES SMD 4.7K OHM 1% 1/10W 0603")
      (fields
        (field (name "TOLERANCE") "±1%")
        (field (name "02. DISTRIBUTOR PART NUMBER") "311-4.70KHRCT-ND")
        (field (name "13. CREATED DATE/NAME") "AUG2018/Hören")
      )
      (libsource (lib "chickenfood") (part "R"))
    )
    (comp (ref "R77")
      (value "4K7")
      (footprint "R0603 Reflow")
      (description "RES SMD 4.7K OHM 1% 1/10W 0603")
      (fields
        (field (name "TOLERANCE") "±1%")
        (field (name "02. DISTRIBUTOR PART NUMBER") "311-4.70KHRCT-ND")
        (field (name "13. CREATED DATE/NAME") "AUG2018/Hören")
      )
      (libsource (lib "chickenfood") (part "R"))
    )
    (comp (ref "R78")
      (value "4K7")
      (footprint "R0603 Reflow")
      (description "RES SMD 4.7K OHM 1% 1/10W 0603")
      (fields
        (field (name "TOLERANCE") "±1%")
        (field (name "02. DISTRIBUTOR PART NUMBER") "311-4.70KHRCT-ND")
        (field (name "13. CREATED DATE/NAME") "AUG2018/Hören")
      )
      (libsource (lib "chickenfood") (part "R"))
    )
    (comp (ref "R79")
      (value "4K7")
      (footprint "R0603 Reflow")
      (description "RES SMD 4.7K OHM 1% 1/10W 0603")
      (fields
        (field (name "TOLERANCE") "±1%")
        (field (name "02. DISTRIBUTOR PART NUMBER") "311-4.70KHRCT-ND")
        (field (name "13. CREATED DATE/NAME") "AUG2018/Hören")
      )
      (libsource (lib "chickenfood") (part "R"))
    )
    (comp (ref "R80")
      (value "4K7")
      (footprint "R0603 Reflow")
      (description "RES SMD 4.7K OHM 1% 1/10W 0603")
      (fields
        (field (name "TOLERANCE") "±1%")
        (field (name "02. DISTRIBUTOR PART NUMBER") "311-4.70KHRCT-ND")
        (field (name "13. CREATED DATE/NAME") "AUG2018/Hören")
      )
      (libsource (lib "chickenfood") (part "R"))
    )
    (comp (ref "R81")
      (value "4K7")
      (footprint "R0603 Reflow")
      (description "RES SMD 4.7K OHM 1% 1/10W 0603")
      (fields
        (field (name "TOLERANCE") "±1%")
        (field (name "02. DISTRIBUTOR PART NUMBER") "311-4.70KHRCT-ND")
        (field (name "13. CREATED DATE/NAME") "AUG2018/Hören")
      )
      (libsource (lib "chickenfood") (part "R"))
    )
    (comp (ref "R82")
      (value "4K7")
      (footprint "R0603 Reflow")
      (description "RES SMD 4.7K OHM 1% 1/10W 0603")
      (fields
        (field (name "TOLERANCE") "±1%")
        (field (name "02. DISTRIBUTOR PART NUMBER") "311-4.70KHRCT-ND")
        (field (name "13. CREATED DATE/NAME") "AUG2018/Hören")
      )
      (libsource (lib "chickenfood") (part "R"))
    )
    (comp (ref "R83")
      (value "4K7")
      (footprint "R0603 Reflow")
      (description "RES SMD 4.7K OHM 1% 1/10W 0603")
      (fields
        (field (name "TOLERANCE") "±1%")
        (field (name "02. DISTRIBUTOR PART NUMBER") "311-4.70KHRCT-ND")
        (field (name "13. CREATED DATE/NAME") "AUG2018/Hören")
      )
      (libsource (lib "chickenfood") (part "R"))
    )
    (comp (ref "R84")
      (value "4K7")
      (footprint "R0603 Reflow")
      (description "RES SMD 4.7K OHM 1% 1/10W 0603")
      (fields
        (field (name "TOLERANCE") "±1%")
        (field (name "02. DISTRIBUTOR PART NUMBER") "311-4.70KHRCT-ND")
        (field (name "13. CREATED DATE/NAME") "AUG2018/Hören")
      )
      (libsource (lib "chickenfood") (part "R"))
    )
    (comp (ref "R85")
      (value "4K7")
      (footprint "R0603 Reflow")
      (description "RES SMD 4.7K OHM 1% 1/10W 0603")
      (fields
        (field (name "TOLERANCE") "±1%")
        (field (name "02. DISTRIBUTOR PART NUMBER") "311-4.70KHRCT-ND")
        (field (name "13. CREATED DATE/NAME") "AUG2018/Hören")
      )
      (libsource (lib "chickenfood") (part "R"))
    )
    (comp (ref "R86")
      (value "4K7")
      (footprint "R0603 Reflow")
      (description "RES SMD 4.7K OHM 1% 1/10W 0603")
      (fields
        (field (name "TOLERANCE") "±1%")
        (field (name "02. DISTRIBUTOR PART NUMBER") "311-4.70KHRCT-ND")
        (field (name "13. CREATED DATE/NAME") "AUG2018/Hören")
      )
      (libsource (lib "chickenfood") (part "R"))
    )
    (comp (ref "R87")
      (value "4K7")
      (footprint "R0603 Reflow")
      (description "RES SMD 4.7K OHM 1% 1/10W 0603")
      (fields
        (field (name "TOLERANCE") "±1%")
        (field (name "02. DISTRIBUTOR PART NUMBER") "311-4.70KHRCT-ND")
        (field (name "13. CREATED DATE/NAME") "AUG2018/Hören")
      )
      (libsource (lib "chickenfood") (part "R"))
    )
    (comp (ref "R88")
      (value "4K7")
      (footprint "R0603 Reflow")
      (description "RES SMD 4.7K OHM 1% 1/10W 0603")
      (fields
        (field (name "TOLERANCE") "±1%")
        (field (name "02. DISTRIBUTOR PART NUMBER") "311-4.70KHRCT-ND")
        (field (name "13. CREATED DATE/NAME") "AUG2018/Hören")
      )
      (libsource (lib "chickenfood") (part "R"))
    )
    (comp (ref "R89")
      (value "4K7")
      (footprint "R0603 Reflow")
      (description "RES SMD 4.7K OHM 1% 1/10W 0603")
      (fields
        (field (name "TOLERANCE") "±1%")
        (field (name "02. DISTRIBUTOR PART NUMBER") "311-4.70KHRCT-ND")
        (field (name "13. CREATED DATE/NAME") "AUG2018/Hören")
      )
      (libsource (lib "chickenfood") (part "R"))
    )
    (comp (ref "R90")
      (value "4K7")
      (footprint "R0603 Reflow")
      (description "RES SMD 4.7K OHM 1% 1/10W 0603")
      (fields
        (field (name "TOLERANCE") "±1%")
        (field (name "02. DISTRIBUTOR PART NUMBER") "311-4.70KHRCT-ND")
        (field (name "13. CREATED DATE/NAME") "AUG2018/Hören")
      )
      (libsource (lib "chickenfood") (part "R"))
    )
    (comp (ref "R91")
      (value "4K7")
      (footprint "R0603 Reflow")
      (description "RES SMD 4.7K OHM 1% 1/10W 0603")
      (fields
        (field (name "TOLERANCE") "±1%")
        (field (name "02. DISTRIBUTOR PART NUMBER") "311-4.70KHRCT-ND")
        (field (name "13. CREATED DATE/NAME") "AUG2018/Hören")
      )
      (libsource (lib "chickenfood") (part "R"))
    )
    (comp (ref "R92")
      (value "4K7")
      (footprint "R0603 Reflow")
      (description "RES SMD 4.7K OHM 1% 1/10W 0603")
      (fields
        (field (name "TOLERANCE") "±1%")
        (field (name "02. DISTRIBUTOR PART NUMBER") "311-4.70KHRCT-ND")
        (field (name "13. CREATED DATE/NAME") "AUG2018/Hören")
      )
      (libsource (lib "chickenfood") (part "R"))
    )
    (comp (ref "R93")
      (value "4K7")
      (footprint "R0603 Reflow")
      (description "RES SMD 4.7K OHM 1% 1/10W 0603")
      (fields
        (field (name "TOLERANCE") "±1%")
        (field (name "02. DISTRIBUTOR PART NUMBER") "311-4.70KHRCT-ND")
        (field (name "13. CREATED DATE/NAME") "AUG2018/Hören")
      )
      (libsource (lib "chickenfood") (part "R"))
    )
    (comp (ref "R143")
      (value "4K7")
      (footprint "R0603 Reflow")
      (description "RES SMD 4.7K OHM 1% 1/10W 0603")
      (fields
        (field (name "TOLERANCE") "±1%")
        (field (name "02. DISTRIBUTOR PART NUMBER") "311-4.70KHRCT-ND")
        (field (name "13. CREATED DATE/NAME") "AUG2018/Hören")
      )
      (libsource (lib "chickenfood") (part "R"))
    )
    (comp (ref "R144")
      (value "4K7")
      (footprint "R0603 Reflow")
      (description "RES SMD 4.7K OHM 1% 1/10W 0603")
      (fields
        (field (name "TOLERANCE") "±1%")
        (field (name "02. DISTRIBUTOR PART NUMBER") "311-4.70KHRCT-ND")
        (field (name "13. CREATED DATE/NAME") "AUG2018/Hören")
      )
      (libsource (lib "chickenfood") (part "R"))
    )
    (comp (ref "R145")
      (value "4K7")
      (footprint "R0603 Reflow")
      (description "RES SMD 4.7K OHM 1% 1/10W 0603")
      (fields
        (field (name "TOLERANCE") "±1%")
        (field (name "02. DISTRIBUTOR PART NUMBER") "311-4.70KHRCT-ND")
        (field (name "13. CREATED DATE/NAME") "AUG2018/Hören")
      )
      (libsource (lib "chickenfood") (part "R"))
    )
    (comp (ref "R146")
      (value "4K7")
      (footprint "R0603 Reflow")
      (description "RES SMD 4.7K OHM 1% 1/10W 0603")
      (fields
        (field (name "TOLERANCE") "±1%")
        (field (name "02. DISTRIBUTOR PART NUMBER") "311-4.70KHRCT-ND")
        (field (name "13. CREATED DATE/NAME") "AUG2018/Hören")
      )
      (libsource (lib "chickenfood") (part "R"))
    )
    (comp (ref "R147")
      (value "4K7")
      (footprint "R0603 Reflow")
      (description "RES SMD 4.7K OHM 1% 1/10W 0603")
      (fields
        (field (name "TOLERANCE") "±1%")
        (field (name "02. DISTRIBUTOR PART NUMBER") "311-4.70KHRCT-ND")
        (field (name "13. CREATED DATE/NAME") "AUG2018/Hören")
      )
      (libsource (lib "chickenfood") (part "R"))
    )
    (comp (ref "R148")
      (value "4K7")
      (footprint "R0603 Reflow")
      (description "RES SMD 4.7K OHM 1% 1/10W 0603")
      (fields
        (field (name "TOLERANCE") "±1%")
        (field (name "02. DISTRIBUTOR PART NUMBER") "311-4.70KHRCT-ND")
        (field (name "13. CREATED DATE/NAME") "AUG2018/Hören")
      )
      (libsource (lib "chickenfood") (part "R"))
    )
    (comp (ref "R149")
      (value "4K7")
      (footprint "R0603 Reflow")
      (description "RES SMD 4.7K OHM 1% 1/10W 0603")
      (fields
        (field (name "TOLERANCE") "±1%")
        (field (name "02. DISTRIBUTOR PART NUMBER") "311-4.70KHRCT-ND")
        (field (name "13. CREATED DATE/NAME") "AUG2018/Hören")
      )
      (libsource (lib "chickenfood") (part "R"))
    )
    (comp (ref "R150")
      (value "4K7")
      (footprint "R0603 Reflow")
      (description "RES SMD 4.7K OHM 1% 1/10W 0603")
      (fields
        (field (name "TOLERANCE") "±1%")
        (field (name "02. DISTRIBUTOR PART NUMBER") "311-4.70KHRCT-ND")
        (field (name "13. CREATED DATE/NAME") "AUG2018/Hören")
      )
      (libsource (lib "chickenfood") (part "R"))
    )
    (comp (ref "R151")
      (value "4K7")
      (footprint "R0603 Reflow")
      (description "RES SMD 4.7K OHM 1% 1/10W 0603")
      (fields
        (field (name "TOLERANCE") "±1%")
        (field (name "02. DISTRIBUTOR PART NUMBER") "311-4.70KHRCT-ND")
        (field (name "13. CREATED DATE/NAME") "AUG2018/Hören")
      )
      (libsource (lib "chickenfood") (part "R"))
    )
    (comp (ref "R152")
      (value "4K7")
      (footprint "R0603 Reflow")
      (description "RES SMD 4.7K OHM 1% 1/10W 0603")
      (fields
        (field (name "TOLERANCE") "±1%")
        (field (name "02. DISTRIBUTOR PART NUMBER") "311-4.70KHRCT-ND")
        (field (name "13. CREATED DATE/NAME") "AUG2018/Hören")
      )
      (libsource (lib "chickenfood") (part "R"))
    )
    (comp (ref "R153")
      (value "4K7")
      (footprint "R0603 Reflow")
      (description "RES SMD 4.7K OHM 1% 1/10W 0603")
      (fields
        (field (name "TOLERANCE") "±1%")
        (field (name "02. DISTRIBUTOR PART NUMBER") "311-4.70KHRCT-ND")
        (field (name "13. CREATED DATE/NAME") "AUG2018/Hören")
      )
      (libsource (lib "chickenfood") (part "R"))
    )
    (comp (ref "R154")
      (value "4K7")
      (footprint "R0603 Reflow")
      (description "RES SMD 4.7K OHM 1% 1/10W 0603")
      (fields
        (field (name "TOLERANCE") "±1%")
        (field (name "02. DISTRIBUTOR PART NUMBER") "311-4.70KHRCT-ND")
        (field (name "13. CREATED DATE/NAME") "AUG2018/Hören")
      )
      (libsource (lib "chickenfood") (part "R"))
    )
    (comp (ref "R155")
      (value "4K7")
      (footprint "R0603 Reflow")
      (description "RES SMD 4.7K OHM 1% 1/10W 0603")
      (fields
        (field (name "TOLERANCE") "±1%")
        (field (name "02. DISTRIBUTOR PART NUMBER") "311-4.70KHRCT-ND")
        (field (name "13. CREATED DATE/NAME") "AUG2018/Hören")
      )
      (libsource (lib "chickenfood") (part "R"))
    )
    (comp (ref "R156")
      (value "4K7")
      (footprint "R0603 Reflow")
      (description "RES SMD 4.7K OHM 1% 1/10W 0603")
      (fields
        (field (name "TOLERANCE") "±1%")
        (field (name "02. DISTRIBUTOR PART NUMBER") "311-4.70KHRCT-ND")
        (field (name "13. CREATED DATE/NAME") "AUG2018/Hören")
      )
      (libsource (lib "chickenfood") (part "R"))
    )
    (comp (ref "R157")
      (value "4K7")
      (footprint "R0603 Reflow")
      (description "RES SMD 4.7K OHM 1% 1/10W 0603")
      (fields
        (field (name "TOLERANCE") "±1%")
        (field (name "02. DISTRIBUTOR PART NUMBER") "311-4.70KHRCT-ND")
        (field (name "13. CREATED DATE/NAME") "AUG2018/Hören")
      )
      (libsource (lib "chickenfood") (part "R"))
    )
    (comp (ref "R158")
      (value "4K7")
      (footprint "R0603 Reflow")
      (description "RES SMD 4.7K OHM 1% 1/10W 0603")
      (fields
        (field (name "TOLERANCE") "±1%")
        (field (name "02. DISTRIBUTOR PART NUMBER") "311-4.70KHRCT-ND")
        (field (name "13. CREATED DATE/NAME") "AUG2018/Hören")
      )
      (libsource (lib "chickenfood") (part "R"))
    )
    (comp (ref "X28")
      (value "X")
      (footprint "TFC-132-01-F-D-LA")
      (description "CONN HEADER TH RA 48POS 1.27MM")
      (fields
        (field (name "02. DISTRIBUTOR PART NUMBER") "TFC-132-01-F-D-LA")
        (field (name "13. CREATED DATE/NAME") "??? / Hören")
      )
      (libsource (lib "PCB-Tester-Board-V1") (part "TFC-132-01-F-D-LA"))
    )
    (comp (ref "X29")
      (value "X")
      (description "32 x 2 x 1.27mm SOCKET DISCRETE CABL COLORED")
      (fields
        (field (name "02. DISTRIBUTOR PART NUMBER") "SFSD-32-30C-G-15.00-S")
        (field (name "13. CREATED DATE/NAME") "??? / Hören")
      )
      (libsource (lib "PCB-Tester-Board-V1") (part "SFSD-32-30C-G-15.00-S"))
    )
    (comp (ref "X30")
      (value "X")
      (footprint "CONFIG64")
      (description "PCB Tester Configuration Matrix for 64 Relays over 8 ABUSes")
      (fields (field (name "13. CREATED DATE/NAME") "??? / Hören"))
      (libsource (lib "PCB-Tester-Board-V1") (part "CONFIG64"))
    )
  )
  (nets
    (net (code "40") (name "/ABUS0") (class "Default")
      (node (ref "X30") (pin "ABUS0") (pinfunction "ABUS0_ABUS0") (pintype "passive"))
    )
    (net (code "41") (name "/ABUS1") (class "Default")
      (node (ref "X30") (pin "ABUS1") (pinfunction "ABUS1_ABUS1") (pintype "passive"))
    )
    (net (code "42") (name "/ABUS2") (class "Default")
      (node (ref "X30") (pin "ABUS2") (pinfunction "ABUS2_ABUS2") (pintype "passive"))
    )
    (net (code "43") (name "/ABUS3") (class "Default")
      (node (ref "X30") (pin "ABUS3") (pinfunction "ABUS3_ABUS3") (pintype "passive"))
    )
    (net (code "44") (name "/ABUS4") (class "Default")
      (node (ref "X30") (pin "ABUS4") (pinfunction "ABUS4_ABUS4") (pintype "passive"))
    )
    (net (code "45") (name "/ABUS5") (class "Default")
      (node (ref "X30") (pin "ABUS5") (pinfunction "ABUS5_ABUS5") (pintype "passive"))
    )
    (net (code "46") (name "/ABUS6") (class "Default")
      (node (ref "X30") (pin "ABUS6") (pinfunction "ABUS6_ABUS6") (pintype "passive"))
    )
    (net (code "47") (name "/ABUS7") (class "Default")
      (node (ref "X30") (pin "ABUS7") (pinfunction "ABUS7_ABUS7") (pintype "passive"))
    )
    (net (code "49") (name "/DRV40") (class "Default")
      (node (ref "Q28") (pin "1") (pinfunction "G_1") (pintype "passive"))
      (node (ref "R33") (pin "2") (pinfunction "2_2") (pintype "passive"))
    )
    (net (code "50") (name "/DRV41") (class "Default")
      (node (ref "Q31") (pin "1") (pinfunction "G_1") (pintype "passive"))
      (node (ref "R48") (pin "2") (pinfunction "2_2") (pintype "passive"))
    )
    (net (code "51") (name "/DRV42") (class "Default")
      (node (ref "Q32") (pin "1") (pinfunction "G_1") (pintype "passive"))
      (node (ref "R49") (pin "2") (pinfunction "2_2") (pintype "passive"))
    )
    (net (code "52") (name "/DRV43") (class "Default")
      (node (ref "Q33") (pin "1") (pinfunction "G_1") (pintype "passive"))
      (node (ref "R50") (pin "2") (pinfunction "2_2") (pintype "passive"))
    )
    (net (code "53") (name "/DRV44") (class "Default")
      (node (ref "Q34") (pin "1") (pinfunction "G_1") (pintype "passive"))
      (node (ref "R51") (pin "2") (pinfunction "2_2") (pintype "passive"))
    )
    (net (code "54") (name "/DRV45") (class "Default")
      (node (ref "Q35") (pin "1") (pinfunction "G_1") (pintype "passive"))
      (node (ref "R52") (pin "2") (pinfunction "2_2") (pintype "passive"))
    )
    (net (code "55") (name "/DRV46") (class "Default")
      (node (ref "Q36") (pin "1") (pinfunction "G_1") (pintype "passive"))
      (node (ref "R53") (pin "2") (pinfunction "2_2") (pintype "passive"))
    )
    (net (code "56") (name "/DRV47") (class "Default")
      (node (ref "Q37") (pin "1") (pinfunction "G_1") (pintype "passive"))
      (node (ref "R54") (pin "2") (pinfunction "2_2") (pintype "passive"))
    )
    (net (code "57") (name "/DRV48") (class "Default")
      (node (ref "Q38") (pin "1") (pinfunction "G_1") (pintype "passive"))
      (node (ref "R55") (pin "2") (pinfunction "2_2") (pintype "passive"))
    )
    (net (code "58") (name "/DRV49") (class "Default")
      (node (ref "Q39") (pin "1") (pinfunction "G_1") (pintype "passive"))
      (node (ref "R56") (pin "2") (pinfunction "2_2") (pintype "passive"))
    )
    (net (code "59") (name "/DRV50") (class "Default")
      (node (ref "Q40") (pin "1") (pinfunction "G_1") (pintype "passive"))
      (node (ref "R57") (pin "2") (pinfunction "2_2") (pintype "passive"))
    )
    (net (code "60") (name "/DRV51") (class "Default")
      (node (ref "Q41") (pin "1") (pinfunction "G_1") (pintype "passive"))
      (node (ref "R58") (pin "2") (pinfunction "2_2") (pintype "passive"))
    )
    (net (code "61") (name "/DRV52") (class "Default")
      (node (ref "Q42") (pin "1") (pinfunction "G_1") (pintype "passive"))
      (node (ref "R59") (pin "2") (pinfunction "2_2") (pintype "passive"))
    )
    (net (code "62") (name "/DRV53") (class "Default")
      (node (ref "Q43") (pin "1") (pinfunction "G_1") (pintype "passive"))
      (node (ref "R60") (pin "2") (pinfunction "2_2") (pintype "passive"))
    )
    (net (code "63") (name "/DRV54") (class "Default")
      (node (ref "Q44") (pin "1") (pinfunction "G_1") (pintype "passive"))
      (node (ref "R61") (pin "2") (pinfunction "2_2") (pintype "passive"))
    )
    (net (code "64") (name "/DRV55") (class "Default")
      (node (ref "Q45") (pin "1") (pinfunction "G_1") (pintype "passive"))
      (node (ref "R62") (pin "2") (pinfunction "2_2") (pintype "passive"))
    )
    (net (code "65") (name "/DRV56") (class "Default")
      (node (ref "Q27") (pin "1") (pinfunction "G_1") (pintype "passive"))
      (node (ref "R32") (pin "2") (pinfunction "2_2") (pintype "passive"))
    )
    (net (code "66") (name "/DRV57") (class "Default")
      (node (ref "Q46") (pin "1") (pinfunction "G_1") (pintype "passive"))
      (node (ref "R63") (pin "2") (pinfunction "2_2") (pintype "passive"))
    )
    (net (code "67") (name "/DRV58") (class "Default")
      (node (ref "Q47") (pin "1") (pinfunction "G_1") (pintype "passive"))
      (node (ref "R64") (pin "2") (pinfunction "2_2") (pintype "passive"))
    )
    (net (code "68") (name "/DRV59") (class "Default")
      (node (ref "Q48") (pin "1") (pinfunction "G_1") (pintype "passive"))
      (node (ref "R65") (pin "2") (pinfunction "2_2") (pintype "passive"))
    )
    (net (code "69") (name "/DRV60") (class "Default")
      (node (ref "Q49") (pin "1") (pinfunction "G_1") (pintype "passive"))
      (node (ref "R66") (pin "2") (pinfunction "2_2") (pintype "passive"))
    )
    (net (code "70") (name "/DRV61") (class "Default")
      (node (ref "Q50") (pin "1") (pinfunction "G_1") (pintype "passive"))
      (node (ref "R67") (pin "2") (pinfunction "2_2") (pintype "passive"))
    )
    (net (code "71") (name "/DRV62") (class "Default")
      (node (ref "Q51") (pin "1") (pinfunction "G_1") (pintype "passive"))
      (node (ref "R68") (pin "2") (pinfunction "2_2") (pintype "passive"))
    )
    (net (code "72") (name "/DRV63") (class "Default")
      (node (ref "Q52") (pin "1") (pinfunction "G_1") (pintype "passive"))
      (node (ref "R69") (pin "2") (pinfunction "2_2") (pintype "passive"))
    )
    (net (code "73") (name "/DRV64") (class "Default")
      (node (ref "Q53") (pin "1") (pinfunction "G_1") (pintype "passive"))
      (node (ref "R70") (pin "2") (pinfunction "2_2") (pintype "passive"))
    )
    (net (code "74") (name "/DRV65") (class "Default")
      (node (ref "Q54") (pin "1") (pinfunction "G_1") (pintype "passive"))
      (node (ref "R71") (pin "2") (pinfunction "2_2") (pintype "passive"))
    )
    (net (code "75") (name "/DRV66") (class "Default")
      (node (ref "Q55") (pin "1") (pinfunction "G_1") (pintype "passive"))
      (node (ref "R72") (pin "2") (pinfunction "2_2") (pintype "passive"))
    )
    (net (code "76") (name "/DRV67") (class "Default")
      (node (ref "Q56") (pin "1") (pinfunction "G_1") (pintype "passive"))
      (node (ref "R73") (pin "2") (pinfunction "2_2") (pintype "passive"))
    )
    (net (code "77") (name "/DRV68") (class "Default")
      (node (ref "Q57") (pin "1") (pinfunction "G_1") (pintype "passive"))
      (node (ref "R74") (pin "2") (pinfunction "2_2") (pintype "passive"))
    )
    (net (code "78") (name "/DRV69") (class "Default")
      (node (ref "Q58") (pin "1") (pinfunction "G_1") (pintype "passive"))
      (node (ref "R75") (pin "2") (pinfunction "2_2") (pintype "passive"))
    )
    (net (code "79") (name "/DRV70") (class "Default")
      (node (ref "Q59") (pin "1") (pinfunction "G_1") (pintype "passive"))
      (node (ref "R76") (pin "2") (pinfunction "2_2") (pintype "passive"))
    )
    (net (code "80") (name "/DRV71") (class "Default")
      (node (ref "Q60") (pin "1") (pinfunction "G_1") (pintype "passive"))
      (node (ref "R77") (pin "2") (pinfunction "2_2") (pintype "passive"))
    )
    (net (code "81") (name "/DRV72") (class "Default")
      (node (ref "Q61") (pin "1") (pinfunction "G_1") (pintype "passive"))
      (node (ref "R78") (pin "2") (pinfunction "2_2") (pintype "passive"))
    )
    (net (code "82") (name "/DRV73") (class "Default")
      (node (ref "Q62") (pin "1") (pinfunction "G_1") (pintype "passive"))
      (node (ref "R79") (pin "2") (pinfunction "2_2") (pintype "passive"))
    )
    (net (code "83") (name "/DRV74") (class "Default")
      (node (ref "Q63") (pin "1") (pinfunction "G_1") (pintype "passive"))
      (node (ref "R80") (pin "2") (pinfunction "2_2") (pintype "passive"))
    )
    (net (code "84") (name "/DRV75") (class "Default")
      (node (ref "Q64") (pin "1") (pinfunction "G_1") (pintype "passive"))
      (node (ref "R81") (pin "2") (pinfunction "2_2") (pintype "passive"))
    )
    (net (code "85") (name "/DRV76") (class "Default")
      (node (ref "Q65") (pin "1") (pinfunction "G_1") (pintype "passive"))
      (node (ref "R82") (pin "2") (pinfunction "2_2") (pintype "passive"))
    )
    (net (code "86") (name "/DRV77") (class "Default")
      (node (ref "Q66") (pin "1") (pinfunction "G_1") (pintype "passive"))
      (node (ref "R83") (pin "2") (pinfunction "2_2") (pintype "passive"))
    )
    (net (code "87") (name "/DRV78") (class "Default")
      (node (ref "Q67") (pin "1") (pinfunction "G_1") (pintype "passive"))
      (node (ref "R84") (pin "2") (pinfunction "2_2") (pintype "passive"))
    )
    (net (code "88") (name "/DRV79") (class "Default")
      (node (ref "Q68") (pin "1") (pinfunction "G_1") (pintype "passive"))
      (node (ref "R85") (pin "2") (pinfunction "2_2") (pintype "passive"))
    )
    (net (code "89") (name "/DRV80") (class "Default")
      (node (ref "Q69") (pin "1") (pinfunction "G_1") (pintype "passive"))
      (node (ref "R86") (pin "2") (pinfunction "2_2") (pintype "passive"))
    )
    (net (code "90") (name "/DRV81") (class "Default")
      (node (ref "Q70") (pin "1") (pinfunction "G_1") (pintype "passive"))
      (node (ref "R87") (pin "2") (pinfunction "2_2") (pintype "passive"))
    )
    (net (code "91") (name "/DRV82") (class "Default")
      (node (ref "Q71") (pin "1") (pinfunction "G_1") (pintype "passive"))
      (node (ref "R88") (pin "2") (pinfunction "2_2") (pintype "passive"))
    )
    (net (code "92") (name "/DRV83") (class "Default")
      (node (ref "Q72") (pin "1") (pinfunction "G_1") (pintype "passive"))
      (node (ref "R89") (pin "2") (pinfunction "2_2") (pintype "passive"))
    )
    (net (code "93") (name "/DRV84") (class "Default")
      (node (ref "Q73") (pin "1") (pinfunction "G_1") (pintype "passive"))
      (node (ref "R90") (pin "2") (pinfunction "2_2") (pintype "passive"))
    )
    (net (code "94") (name "/DRV85") (class "Default")
      (node (ref "Q74") (pin "1") (pinfunction "G_1") (pintype "passive"))
      (node (ref "R91") (pin "2") (pinfunction "2_2") (pintype "passive"))
    )
    (net (code "95") (name "/DRV86") (class "Default")
      (node (ref "Q75") (pin "1") (pinfunction "G_1") (pintype "passive"))
      (node (ref "R92") (pin "2") (pinfunction "2_2") (pintype "passive"))
    )
    (net (code "96") (name "/DRV87") (class "Default")
      (node (ref "Q76") (pin "1") (pinfunction "G_1") (pintype "passive"))
      (node (ref "R93") (pin "2") (pinfunction "2_2") (pintype "passive"))
    )
    (net (code "97") (name "/DRV88") (class "Default")
      (node (ref "Q81") (pin "1") (pinfunction "G_1") (pintype "passive"))
      (node (ref "R143") (pin "2") (pinfunction "2_2") (pintype "passive"))
    )
    (net (code "98") (name "/DRV89") (class "Default")
      (node (ref "Q82") (pin "1") (pinfunction "G_1") (pintype "passive"))
      (node (ref "R144") (pin "2") (pinfunction "2_2") (pintype "passive"))
    )
    (net (code "99") (name "/DRV90") (class "Default")
      (node (ref "Q83") (pin "1") (pinfunction "G_1") (pintype "passive"))
      (node (ref "R145") (pin "2") (pinfunction "2_2") (pintype "passive"))
    )
    (net (code "100") (name "/DRV91") (class "Default")
      (node (ref "Q84") (pin "1") (pinfunction "G_1") (pintype "passive"))
      (node (ref "R146") (pin "2") (pinfunction "2_2") (pintype "passive"))
    )
    (net (code "101") (name "/DRV92") (class "Default")
      (node (ref "Q85") (pin "1") (pinfunction "G_1") (pintype "passive"))
      (node (ref "R147") (pin "2") (pinfunction "2_2") (pintype "passive"))
    )
    (net (code "102") (name "/DRV93") (class "Default")
      (node (ref "Q86") (pin "1") (pinfunction "G_1") (pintype "passive"))
      (node (ref "R148") (pin "2") (pinfunction "2_2") (pintype "passive"))
    )
    (net (code "103") (name "/DRV94") (class "Default")
      (node (ref "Q87") (pin "1") (pinfunction "G_1") (pintype "passive"))
      (node (ref "R149") (pin "2") (pinfunction "2_2") (pintype "passive"))
    )
    (net (code "104") (name "/DRV95") (class "Default")
      (node (ref "Q88") (pin "1") (pinfunction "G_1") (pintype "passive"))
      (node (ref "R150") (pin "2") (pinfunction "2_2") (pintype "passive"))
    )
    (net (code "105") (name "/DRV96") (class "Default")
      (node (ref "Q89") (pin "1") (pinfunction "G_1") (pintype "passive"))
      (node (ref "R151") (pin "2") (pinfunction "2_2") (pintype "passive"))
    )
    (net (code "106") (name "/DRV97") (class "Default")
      (node (ref "Q90") (pin "1") (pinfunction "G_1") (pintype "passive"))
      (node (ref "R152") (pin "2") (pinfunction "2_2") (pintype "passive"))
    )
    (net (code "107") (name "/DRV98") (class "Default")
      (node (ref "Q91") (pin "1") (pinfunction "G_1") (pintype "passive"))
      (node (ref "R153") (pin "2") (pinfunction "2_2") (pintype "passive"))
    )
    (net (code "108") (name "/DRV99") (class "Default")
      (node (ref "Q92") (pin "1") (pinfunction "G_1") (pintype "passive"))
      (node (ref "R154") (pin "2") (pinfunction "2_2") (pintype "passive"))
    )
    (net (code "109") (name "/DRV100") (class "Default")
      (node (ref "Q93") (pin "1") (pinfunction "G_1") (pintype "passive"))
      (node (ref "R155") (pin "2") (pinfunction "2_2") (pintype "passive"))
    )
    (net (code "110") (name "/DRV101") (class "Default")
      (node (ref "Q94") (pin "1") (pinfunction "G_1") (pintype "passive"))
      (node (ref "R156") (pin "2") (pinfunction "2_2") (pintype "passive"))
    )
    (net (code "111") (name "/DRV102") (class "Default")
      (node (ref "Q95") (pin "1") (pinfunction "G_1") (pintype "passive"))
      (node (ref "R157") (pin "2") (pinfunction "2_2") (pintype "passive"))
    )
    (net (code "112") (name "/DRV103") (class "Default")
      (node (ref "Q96") (pin "1") (pinfunction "G_1") (pintype "passive"))
      (node (ref "R158") (pin "2") (pinfunction "2_2") (pintype "passive"))
    )
    (net (code "114") (name "5V0R") (class "Default")
      (node (ref "K28") (pin "1") (pinfunction "+_1") (pintype "passive"))
      (node (ref "K29") (pin "1") (pinfunction "+_1") (pintype "passive"))
      (node (ref "K30") (pin "1") (pinfunction "+_1") (pintype "passive"))
      (node (ref "K31") (pin "1") (pinfunction "+_1") (pintype "passive"))
      (node (ref "K32") (pin "1") (pinfunction "+_1") (pintype "passive"))
      (node (ref "K33") (pin "1") (pinfunction "+_1") (pintype "passive"))
      (node (ref "K34") (pin "1") (pinfunction "+_1") (pintype "passive"))
      (node (ref "K35") (pin "1") (pinfunction "+_1") (pintype "passive"))
      (node (ref "K36") (pin "1") (pinfunction "+_1") (pintype "passive"))
      (node (ref "K37") (pin "1") (pinfunction "+_1") (pintype "passive"))
      (node (ref "K38") (pin "1") (pinfunction "+_1") (pintype "passive"))
      (node (ref "K39") (pin "1") (pinfunction "+_1") (pintype "passive"))
      (node (ref "K40") (pin "1") (pinfunction "+_1") (pintype "passive"))
      (node (ref "K41") (pin "1") (pinfunction "+_1") (pintype "passive"))
      (node (ref "K42") (pin "1") (pinfunction "+_1") (pintype "passive"))
      (node (ref "K43") (pin "1") (pinfunction "+_1") (pintype "passive"))
      (node (ref "K44") (pin "1") (pinfunction "+_1") (pintype "passive"))
      (node (ref "K45") (pin "1") (pinfunction "+_1") (pintype "passive"))
      (node (ref "K46") (pin "1") (pinfunction "+_1") (pintype "passive"))
      (node (ref "K47") (pin "1") (pinfunction "+_1") (pintype "passive"))
      (node (ref "K48") (pin "1") (pinfunction "+_1") (pintype "passive"))
      (node (ref "K49") (pin "1") (pinfunction "+_1") (pintype "passive"))
      (node (ref "K50") (pin "1") (pinfunction "+_1") (pintype "passive"))
      (node (ref "K51") (pin "1") (pinfunction "+_1") (pintype "passive"))
      (node (ref "K52") (pin "1") (pinfunction "+_1") (pintype "passive"))
      (node (ref "K53") (pin "1") (pinfunction "+_1") (pintype "passive"))
      (node (ref "K54") (pin "1") (pinfunction "+_1") (pintype "passive"))
      (node (ref "K55") (pin "1") (pinfunction "+_1") (pintype "passive"))
      (node (ref "K56") (pin "1") (pinfunction "+_1") (pintype "passive"))
      (node (ref "K57") (pin "1") (pinfunction "+_1") (pintype "passive"))
      (node (ref "K58") (pin "1") (pinfunction "+_1") (pintype "passive"))
      (node (ref "K59") (pin "1") (pinfunction "+_1") (pintype "passive"))
      (node (ref "K60") (pin "1") (pinfunction "+_1") (pintype "passive"))
      (node (ref "K61") (pin "1") (pinfunction "+_1") (pintype "passive"))
      (node (ref "K62") (pin "1") (pinfunction "+_1") (pintype "passive"))
      (node (ref "K63") (pin "1") (pinfunction "+_1") (pintype "passive"))
      (node (ref "K64") (pin "1") (pinfunction "+_1") (pintype "passive"))
      (node (ref "K65") (pin "1") (pinfunction "+_1") (pintype "passive"))
      (node (ref "K66") (pin "1") (pinfunction "+_1") (pintype "passive"))
      (node (ref "K67") (pin "1") (pinfunction "+_1") (pintype "passive"))
      (node (ref "K68") (pin "1") (pinfunction "+_1") (pintype "passive"))
      (node (ref "K69") (pin "1") (pinfunction "+_1") (pintype "passive"))
      (node (ref "K70") (pin "1") (pinfunction "+_1") (pintype "passive"))
      (node (ref "K71") (pin "1") (pinfunction "+_1") (pintype "passive"))
      (node (ref "K72") (pin "1") (pinfunction "+_1") (pintype "passive"))
      (node (ref "K73") (pin "1") (pinfunction "+_1") (pintype "passive"))
      (node (ref "K74") (pin "1") (pinfunction "+_1") (pintype "passive"))
      (node (ref "K75") (pin "1") (pinfunction "+_1") (pintype "passive"))
      (node (ref "K76") (pin "1") (pinfunction "+_1") (pintype "passive"))
      (node (ref "K77") (pin "1") (pinfunction "+_1") (pintype "passive"))
      (node (ref "K78") (pin "1") (pinfunction "+_1") (pintype "passive"))
      (node (ref "K79") (pin "1") (pinfunction "+_1") (pintype "passive"))
      (node (ref "K80") (pin "1") (pinfunction "+_1") (pintype "passive"))
      (node (ref "K81") (pin "1") (pinfunction "+_1") (pintype "passive"))
      (node (ref "K82") (pin "1") (pinfunction "+_1") (pintype "passive"))
      (node (ref "K83") (pin "1") (pinfunction "+_1") (pintype "passive"))
      (node (ref "K84") (pin "1") (pinfunction "+_1") (pintype "passive"))
      (node (ref "K85") (pin "1") (pinfunction "+_1") (pintype "passive"))
      (node (ref "K86") (pin "1") (pinfunction "+_1") (pintype "passive"))
      (node (ref "K87") (pin "1") (pinfunction "+_1") (pintype "passive"))
      (node (ref "K88") (pin "1") (pinfunction "+_1") (pintype "passive"))
      (node (ref "K89") (pin "1") (pinfunction "+_1") (pintype "passive"))
      (node (ref "K90") (pin "1") (pinfunction "+_1") (pintype "passive"))
      (node (ref "K91") (pin "1") (pinfunction "+_1") (pintype "passive"))
    )
    (net (code "115") (name "GND") (class "Default")
      (node (ref "Q27") (pin "2") (pinfunction "S_2") (pintype "passive"))
      (node (ref "Q28") (pin "2") (pinfunction "S_2") (pintype "passive"))
      (node (ref "Q31") (pin "2") (pinfunction "S_2") (pintype "passive"))
      (node (ref "Q32") (pin "2") (pinfunction "S_2") (pintype "passive"))
      (node (ref "Q33") (pin "2") (pinfunction "S_2") (pintype "passive"))
      (node (ref "Q34") (pin "2") (pinfunction "S_2") (pintype "passive"))
      (node (ref "Q35") (pin "2") (pinfunction "S_2") (pintype "passive"))
      (node (ref "Q36") (pin "2") (pinfunction "S_2") (pintype "passive"))
      (node (ref "Q37") (pin "2") (pinfunction "S_2") (pintype "passive"))
      (node (ref "Q38") (pin "2") (pinfunction "S_2") (pintype "passive"))
      (node (ref "Q39") (pin "2") (pinfunction "S_2") (pintype "passive"))
      (node (ref "Q40") (pin "2") (pinfunction "S_2") (pintype "passive"))
      (node (ref "Q41") (pin "2") (pinfunction "S_2") (pintype "passive"))
      (node (ref "Q42") (pin "2") (pinfunction "S_2") (pintype "passive"))
      (node (ref "Q43") (pin "2") (pinfunction "S_2") (pintype "passive"))
      (node (ref "Q44") (pin "2") (pinfunction "S_2") (pintype "passive"))
      (node (ref "Q45") (pin "2") (pinfunction "S_2") (pintype "passive"))
      (node (ref "Q46") (pin "2") (pinfunction "S_2") (pintype "passive"))
      (node (ref "Q47") (pin "2") (pinfunction "S_2") (pintype "passive"))
      (node (ref "Q48") (pin "2") (pinfunction "S_2") (pintype "passive"))
      (node (ref "Q49") (pin "2") (pinfunction "S_2") (pintype "passive"))
      (node (ref "Q50") (pin "2") (pinfunction "S_2") (pintype "passive"))
      (node (ref "Q51") (pin "2") (pinfunction "S_2") (pintype "passive"))
      (node (ref "Q52") (pin "2") (pinfunction "S_2") (pintype "passive"))
      (node (ref "Q53") (pin "2") (pinfunction "S_2") (pintype "passive"))
      (node (ref "Q54") (pin "2") (pinfunction "S_2") (pintype "passive"))
      (node (ref "Q55") (pin "2") (pinfunction "S_2") (pintype "passive"))
      (node (ref "Q56") (pin "2") (pinfunction "S_2") (pintype "passive"))
      (node (ref "Q57") (pin "2") (pinfunction "S_2") (pintype "passive"))
      (node (ref "Q58") (pin "2") (pinfunction "S_2") (pintype "passive"))
      (node (ref "Q59") (pin "2") (pinfunction "S_2") (pintype "passive"))
      (node (ref "Q60") (pin "2") (pinfunction "S_2") (pintype "passive"))
      (node (ref "Q61") (pin "2") (pinfunction "S_2") (pintype "passive"))
      (node (ref "Q62") (pin "2") (pinfunction "S_2") (pintype "passive"))
      (node (ref "Q63") (pin "2") (pinfunction "S_2") (pintype "passive"))
      (node (ref "Q64") (pin "2") (pinfunction "S_2") (pintype "passive"))
      (node (ref "Q65") (pin "2") (pinfunction "S_2") (pintype "passive"))
      (node (ref "Q66") (pin "2") (pinfunction "S_2") (pintype "passive"))
      (node (ref "Q67") (pin "2") (pinfunction "S_2") (pintype "passive"))
      (node (ref "Q68") (pin "2") (pinfunction "S_2") (pintype "passive"))
      (node (ref "Q69") (pin "2") (pinfunction "S_2") (pintype "passive"))
      (node (ref "Q70") (pin "2") (pinfunction "S_2") (pintype "passive"))
      (node (ref "Q71") (pin "2") (pinfunction "S_2") (pintype "passive"))
      (node (ref "Q72") (pin "2") (pinfunction "S_2") (pintype "passive"))
      (node (ref "Q73") (pin "2") (pinfunction "S_2") (pintype "passive"))
      (node (ref "Q74") (pin "2") (pinfunction "S_2") (pintype "passive"))
      (node (ref "Q75") (pin "2") (pinfunction "S_2") (pintype "passive"))
      (node (ref "Q76") (pin "2") (pinfunction "S_2") (pintype "passive"))
      (node (ref "Q81") (pin "2") (pinfunction "S_2") (pintype "passive"))
      (node (ref "Q82") (pin "2") (pinfunction "S_2") (pintype "passive"))
      (node (ref "Q83") (pin "2") (pinfunction "S_2") (pintype "passive"))
      (node (ref "Q84") (pin "2") (pinfunction "S_2") (pintype "passive"))
      (node (ref "Q85") (pin "2") (pinfunction "S_2") (pintype "passive"))
      (node (ref "Q86") (pin "2") (pinfunction "S_2") (pintype "passive"))
      (node (ref "Q87") (pin "2") (pinfunction "S_2") (pintype "passive"))
      (node (ref "Q88") (pin "2") (pinfunction "S_2") (pintype "passive"))
      (node (ref "Q89") (pin "2") (pinfunction "S_2") (pintype "passive"))
      (node (ref "Q90") (pin "2") (pinfunction "S_2") (pintype "passive"))
      (node (ref "Q91") (pin "2") (pinfunction "S_2") (pintype "passive"))
      (node (ref "Q92") (pin "2") (pinfunction "S_2") (pintype "passive"))
      (node (ref "Q93") (pin "2") (pinfunction "S_2") (pintype "passive"))
      (node (ref "Q94") (pin "2") (pinfunction "S_2") (pintype "passive"))
      (node (ref "Q95") (pin "2") (pinfunction "S_2") (pintype "passive"))
      (node (ref "Q96") (pin "2") (pinfunction "S_2") (pintype "passive"))
      (node (ref "R143") (pin "1") (pinfunction "1_1") (pintype "passive"))
      (node (ref "R144") (pin "1") (pinfunction "1_1") (pintype "passive"))
      (node (ref "R145") (pin "1") (pinfunction "1_1") (pintype "passive"))
      (node (ref "R146") (pin "1") (pinfunction "1_1") (pintype "passive"))
      (node (ref "R147") (pin "1") (pinfunction "1_1") (pintype "passive"))
      (node (ref "R148") (pin "1") (pinfunction "1_1") (pintype "passive"))
      (node (ref "R149") (pin "1") (pinfunction "1_1") (pintype "passive"))
      (node (ref "R150") (pin "1") (pinfunction "1_1") (pintype "passive"))
      (node (ref "R151") (pin "1") (pinfunction "1_1") (pintype "passive"))
      (node (ref "R152") (pin "1") (pinfunction "1_1") (pintype "passive"))
      (node (ref "R153") (pin "1") (pinfunction "1_1") (pintype "passive"))
      (node (ref "R154") (pin "1") (pinfunction "1_1") (pintype "passive"))
      (node (ref "R155") (pin "1") (pinfunction "1_1") (pintype "passive"))
      (node (ref "R156") (pin "1") (pinfunction "1_1") (pintype "passive"))
      (node (ref "R157") (pin "1") (pinfunction "1_1") (pintype "passive"))
      (node (ref "R158") (pin "1") (pinfunction "1_1") (pintype "passive"))
      (node (ref "R32") (pin "1") (pinfunction "1_1") (pintype "passive"))
      (node (ref "R33") (pin "1") (pinfunction "1_1") (pintype "passive"))
      (node (ref "R48") (pin "1") (pinfunction "1_1") (pintype "passive"))
      (node (ref "R49") (pin "1") (pinfunction "1_1") (pintype "passive"))
      (node (ref "R50") (pin "1") (pinfunction "1_1") (pintype "passive"))
      (node (ref "R51") (pin "1") (pinfunction "1_1") (pintype "passive"))
      (node (ref "R52") (pin "1") (pinfunction "1_1") (pintype "passive"))
      (node (ref "R53") (pin "1") (pinfunction "1_1") (pintype "passive"))
      (node (ref "R54") (pin "1") (pinfunction "1_1") (pintype "passive"))
      (node (ref "R55") (pin "1") (pinfunction "1_1") (pintype "passive"))
      (node (ref "R56") (pin "1") (pinfunction "1_1") (pintype "passive"))
      (node (ref "R57") (pin "1") (pinfunction "1_1") (pintype "passive"))
      (node (ref "R58") (pin "1") (pinfunction "1_1") (pintype "passive"))
      (node (ref "R59") (pin "1") (pinfunction "1_1") (pintype "passive"))
      (node (ref "R60") (pin "1") (pinfunction "1_1") (pintype "passive"))
      (node (ref "R61") (pin "1") (pinfunction "1_1") (pintype "passive"))
      (node (ref "R62") (pin "1") (pinfunction "1_1") (pintype "passive"))
      (node (ref "R63") (pin "1") (pinfunction "1_1") (pintype "passive"))
      (node (ref "R64") (pin "1") (pinfunction "1_1") (pintype "passive"))
      (node (ref "R65") (pin "1") (pinfunction "1_1") (pintype "passive"))
      (node (ref "R66") (pin "1") (pinfunction "1_1") (pintype "passive"))
      (node (ref "R67") (pin "1") (pinfunction "1_1") (pintype "passive"))
      (node (ref "R68") (pin "1") (pinfunction "1_1") (pintype "passive"))
      (node (ref "R69") (pin "1") (pinfunction "1_1") (pintype "passive"))
      (node (ref "R70") (pin "1") (pinfunction "1_1") (pintype "passive"))
      (node (ref "R71") (pin "1") (pinfunction "1_1") (pintype "passive"))
      (node (ref "R72") (pin "1") (pinfunction "1_1") (pintype "passive"))
      (node (ref "R73") (pin "1") (pinfunction "1_1") (pintype "passive"))
      (node (ref "R74") (pin "1") (pinfunction "1_1") (pintype "passive"))
      (node (ref "R75") (pin "1") (pinfunction "1_1") (pintype "passive"))
      (node (ref "R76") (pin "1") (pinfunction "1_1") (pintype "passive"))
      (node (ref "R77") (pin "1") (pinfunction "1_1") (pintype "passive"))
      (node (ref "R78") (pin "1") (pinfunction "1_1") (pintype "passive"))
      (node (ref "R79") (pin "1") (pinfunction "1_1") (pintype "passive"))
      (node (ref "R80") (pin "1") (pinfunction "1_1") (pintype "passive"))
      (node (ref "R81") (pin "1") (pinfunction "1_1") (pintype "passive"))
      (node (ref "R82") (pin "1") (pinfunction "1_1") (pintype "passive"))
      (node (ref "R83") (pin "1") (pinfunction "1_1") (pintype "passive"))
      (node (ref "R84") (pin "1") (pinfunction "1_1") (pintype "passive"))
      (node (ref "R85") (pin "1") (pinfunction "1_1") (pintype "passive"))
      (node (ref "R86") (pin "1") (pinfunction "1_1") (pintype "passive"))
      (node (ref "R87") (pin "1") (pinfunction "1_1") (pintype "passive"))
      (node (ref "R88") (pin "1") (pinfunction "1_1") (pintype "passive"))
      (node (ref "R89") (pin "1") (pinfunction "1_1") (pintype "passive"))
      (node (ref "R90") (pin "1") (pinfunction "1_1") (pintype "passive"))
      (node (ref "R91") (pin "1") (pinfunction "1_1") (pintype "passive"))
      (node (ref "R92") (pin "1") (pinfunction "1_1") (pintype "passive"))
      (node (ref "R93") (pin "1") (pinfunction "1_1") (pintype "passive"))
    )
    (net (code "116") (name "Net-(K28A-CA)") (class "Default")
      (node (ref "K28") (pin "3") (pinfunction "CA_3") (pintype "passive"))
      (node (ref "X30") (pin "1") (pinfunction "1_1") (pintype "passive"))
    )
    (net (code "117") (name "Net-(K28A-CB)") (class "Default")
      (node (ref "K28") (pin "4") (pinfunction "CB_4") (pintype "passive"))
      (node (ref "X28") (pin "1") (pinfunction "1_1") (pintype "passive"))
    )
    (net (code "118") (name "Net-(K28B--)") (class "Default")
      (node (ref "K28") (pin "2") (pinfunction "-_2") (pintype "passive"))
      (node (ref "Q28") (pin "3") (pinfunction "D_3") (pintype "passive"))
    )
    (net (code "119") (name "Net-(K29A-CA)") (class "Default")
      (node (ref "K29") (pin "3") (pinfunction "CA_3") (pintype "passive"))
      (node (ref "X30") (pin "2") (pinfunction "2_2") (pintype "passive"))
    )
    (net (code "120") (name "Net-(K29A-CB)") (class "Default")
      (node (ref "K29") (pin "4") (pinfunction "CB_4") (pintype "passive"))
      (node (ref "X28") (pin "2") (pinfunction "2_2") (pintype "passive"))
    )
    (net (code "121") (name "Net-(K29B--)") (class "Default")
      (node (ref "K29") (pin "2") (pinfunction "-_2") (pintype "passive"))
      (node (ref "Q31") (pin "3") (pinfunction "D_3") (pintype "passive"))
    )
    (net (code "122") (name "Net-(K30A-CA)") (class "Default")
      (node (ref "K30") (pin "3") (pinfunction "CA_3") (pintype "passive"))
      (node (ref "X30") (pin "3") (pinfunction "3_3") (pintype "passive"))
    )
    (net (code "123") (name "Net-(K30A-CB)") (class "Default")
      (node (ref "K30") (pin "4") (pinfunction "CB_4") (pintype "passive"))
      (node (ref "X28") (pin "3") (pinfunction "3_3") (pintype "passive"))
    )
    (net (code "124") (name "Net-(K30B--)") (class "Default")
      (node (ref "K30") (pin "2") (pinfunction "-_2") (pintype "passive"))
      (node (ref "Q32") (pin "3") (pinfunction "D_3") (pintype "passive"))
    )
    (net (code "125") (name "Net-(K31A-CA)") (class "Default")
      (node (ref "K31") (pin "3") (pinfunction "CA_3") (pintype "passive"))
      (node (ref "X30") (pin "4") (pinfunction "4_4") (pintype "passive"))
    )
    (net (code "126") (name "Net-(K31A-CB)") (class "Default")
      (node (ref "K31") (pin "4") (pinfunction "CB_4") (pintype "passive"))
      (node (ref "X28") (pin "4") (pinfunction "4_4") (pintype "passive"))
    )
    (net (code "127") (name "Net-(K31B--)") (class "Default")
      (node (ref "K31") (pin "2") (pinfunction "-_2") (pintype "passive"))
      (node (ref "Q33") (pin "3") (pinfunction "D_3") (pintype "passive"))
    )
    (net (code "128") (name "Net-(K32A-CA)") (class "Default")
      (node (ref "K32") (pin "3") (pinfunction "CA_3") (pintype "passive"))
      (node (ref "X30") (pin "5") (pinfunction "5_5") (pintype "passive"))
    )
    (net (code "129") (name "Net-(K32A-CB)") (class "Default")
      (node (ref "K32") (pin "4") (pinfunction "CB_4") (pintype "passive"))
      (node (ref "X28") (pin "5") (pinfunction "5_5") (pintype "passive"))
    )
    (net (code "130") (name "Net-(K32B--)") (class "Default")
      (node (ref "K32") (pin "2") (pinfunction "-_2") (pintype "passive"))
      (node (ref "Q34") (pin "3") (pinfunction "D_3") (pintype "passive"))
    )
    (net (code "131") (name "Net-(K33A-CA)") (class "Default")
      (node (ref "K33") (pin "3") (pinfunction "CA_3") (pintype "passive"))
      (node (ref "X30") (pin "6") (pinfunction "6_6") (pintype "passive"))
    )
    (net (code "132") (name "Net-(K33A-CB)") (class "Default")
      (node (ref "K33") (pin "4") (pinfunction "CB_4") (pintype "passive"))
      (node (ref "X28") (pin "6") (pinfunction "6_6") (pintype "passive"))
    )
    (net (code "133") (name "Net-(K33B--)") (class "Default")
      (node (ref "K33") (pin "2") (pinfunction "-_2") (pintype "passive"))
      (node (ref "Q35") (pin "3") (pinfunction "D_3") (pintype "passive"))
    )
    (net (code "134") (name "Net-(K34A-CA)") (class "Default")
      (node (ref "K34") (pin "3") (pinfunction "CA_3") (pintype "passive"))
      (node (ref "X30") (pin "7") (pinfunction "7_7") (pintype "passive"))
    )
    (net (code "135") (name "Net-(K34A-CB)") (class "Default")
      (node (ref "K34") (pin "4") (pinfunction "CB_4") (pintype "passive"))
      (node (ref "X28") (pin "7") (pinfunction "7_7") (pintype "passive"))
    )
    (net (code "136") (name "Net-(K34B--)") (class "Default")
      (node (ref "K34") (pin "2") (pinfunction "-_2") (pintype "passive"))
      (node (ref "Q36") (pin "3") (pinfunction "D_3") (pintype "passive"))
    )
    (net (code "137") (name "Net-(K35A-CA)") (class "Default")
      (node (ref "K35") (pin "3") (pinfunction "CA_3") (pintype "passive"))
      (node (ref "X30") (pin "8") (pinfunction "8_8") (pintype "passive"))
    )
    (net (code "138") (name "Net-(K35A-CB)") (class "Default")
      (node (ref "K35") (pin "4") (pinfunction "CB_4") (pintype "passive"))
      (node (ref "X28") (pin "8") (pinfunction "8_8") (pintype "passive"))
    )
    (net (code "139") (name "Net-(K35B--)") (class "Default")
      (node (ref "K35") (pin "2") (pinfunction "-_2") (pintype "passive"))
      (node (ref "Q37") (pin "3") (pinfunction "D_3") (pintype "passive"))
    )
    (net (code "140") (name "Net-(K36A-CA)") (class "Default")
      (node (ref "K36") (pin "3") (pinfunction "CA_3") (pintype "passive"))
      (node (ref "X30") (pin "9") (pinfunction "9_9") (pintype "passive"))
    )
    (net (code "141") (name "Net-(K36A-CB)") (class "Default")
      (node (ref "K36") (pin "4") (pinfunction "CB_4") (pintype "passive"))
      (node (ref "X28") (pin "9") (pinfunction "9_9") (pintype "passive"))
    )
    (net (code "142") (name "Net-(K36B--)") (class "Default")
      (node (ref "K36") (pin "2") (pinfunction "-_2") (pintype "passive"))
      (node (ref "Q38") (pin "3") (pinfunction "D_3") (pintype "passive"))
    )
    (net (code "143") (name "Net-(K37A-CA)") (class "Default")
      (node (ref "K37") (pin "3") (pinfunction "CA_3") (pintype "passive"))
      (node (ref "X30") (pin "10") (pinfunction "10_10") (pintype "passive"))
    )
    (net (code "144") (name "Net-(K37A-CB)") (class "Default")
      (node (ref "K37") (pin "4") (pinfunction "CB_4") (pintype "passive"))
      (node (ref "X28") (pin "10") (pinfunction "10_10") (pintype "passive"))
    )
    (net (code "145") (name "Net-(K37B--)") (class "Default")
      (node (ref "K37") (pin "2") (pinfunction "-_2") (pintype "passive"))
      (node (ref "Q39") (pin "3") (pinfunction "D_3") (pintype "passive"))
    )
    (net (code "146") (name "Net-(K38A-CA)") (class "Default")
      (node (ref "K38") (pin "3") (pinfunction "CA_3") (pintype "passive"))
      (node (ref "X30") (pin "11") (pinfunction "11_11") (pintype "passive"))
    )
    (net (code "147") (name "Net-(K38A-CB)") (class "Default")
      (node (ref "K38") (pin "4") (pinfunction "CB_4") (pintype "passive"))
      (node (ref "X28") (pin "11") (pinfunction "11_11") (pintype "passive"))
    )
    (net (code "148") (name "Net-(K38B--)") (class "Default")
      (node (ref "K38") (pin "2") (pinfunction "-_2") (pintype "passive"))
      (node (ref "Q40") (pin "3") (pinfunction "D_3") (pintype "passive"))
    )
    (net (code "149") (name "Net-(K39A-CA)") (class "Default")
      (node (ref "K39") (pin "3") (pinfunction "CA_3") (pintype "passive"))
      (node (ref "X30") (pin "12") (pinfunction "12_12") (pintype "passive"))
    )
    (net (code "150") (name "Net-(K39A-CB)") (class "Default")
      (node (ref "K39") (pin "4") (pinfunction "CB_4") (pintype "passive"))
      (node (ref "X28") (pin "12") (pinfunction "12_12") (pintype "passive"))
    )
    (net (code "151") (name "Net-(K39B--)") (class "Default")
      (node (ref "K39") (pin "2") (pinfunction "-_2") (pintype "passive"))
      (node (ref "Q41") (pin "3") (pinfunction "D_3") (pintype "passive"))
    )
    (net (code "152") (name "Net-(K40A-CA)") (class "Default")
      (node (ref "K40") (pin "3") (pinfunction "CA_3") (pintype "passive"))
      (node (ref "X30") (pin "13") (pinfunction "13_13") (pintype "passive"))
    )
    (net (code "153") (name "Net-(K40A-CB)") (class "Default")
      (node (ref "K40") (pin "4") (pinfunction "CB_4") (pintype "passive"))
      (node (ref "X28") (pin "13") (pinfunction "13_13") (pintype "passive"))
    )
    (net (code "154") (name "Net-(K40B--)") (class "Default")
      (node (ref "K40") (pin "2") (pinfunction "-_2") (pintype "passive"))
      (node (ref "Q42") (pin "3") (pinfunction "D_3") (pintype "passive"))
    )
    (net (code "155") (name "Net-(K41A-CA)") (class "Default")
      (node (ref "K41") (pin "3") (pinfunction "CA_3") (pintype "passive"))
      (node (ref "X30") (pin "14") (pinfunction "14_14") (pintype "passive"))
    )
    (net (code "156") (name "Net-(K41A-CB)") (class "Default")
      (node (ref "K41") (pin "4") (pinfunction "CB_4") (pintype "passive"))
      (node (ref "X28") (pin "14") (pinfunction "14_14") (pintype "passive"))
    )
    (net (code "157") (name "Net-(K41B--)") (class "Default")
      (node (ref "K41") (pin "2") (pinfunction "-_2") (pintype "passive"))
      (node (ref "Q43") (pin "3") (pinfunction "D_3") (pintype "passive"))
    )
    (net (code "158") (name "Net-(K42A-CA)") (class "Default")
      (node (ref "K42") (pin "3") (pinfunction "CA_3") (pintype "passive"))
      (node (ref "X30") (pin "15") (pinfunction "15_15") (pintype "passive"))
    )
    (net (code "159") (name "Net-(K42A-CB)") (class "Default")
      (node (ref "K42") (pin "4") (pinfunction "CB_4") (pintype "passive"))
      (node (ref "X28") (pin "15") (pinfunction "15_15") (pintype "passive"))
    )
    (net (code "160") (name "Net-(K42B--)") (class "Default")
      (node (ref "K42") (pin "2") (pinfunction "-_2") (pintype "passive"))
      (node (ref "Q44") (pin "3") (pinfunction "D_3") (pintype "passive"))
    )
    (net (code "161") (name "Net-(K43A-CA)") (class "Default")
      (node (ref "K43") (pin "3") (pinfunction "CA_3") (pintype "passive"))
      (node (ref "X30") (pin "16") (pinfunction "16_16") (pintype "passive"))
    )
    (net (code "162") (name "Net-(K43A-CB)") (class "Default")
      (node (ref "K43") (pin "4") (pinfunction "CB_4") (pintype "passive"))
      (node (ref "X28") (pin "16") (pinfunction "16_16") (pintype "passive"))
    )
    (net (code "163") (name "Net-(K43B--)") (class "Default")
      (node (ref "K43") (pin "2") (pinfunction "-_2") (pintype "passive"))
      (node (ref "Q45") (pin "3") (pinfunction "D_3") (pintype "passive"))
    )
    (net (code "164") (name "Net-(K44A-CA)") (class "Default")
      (node (ref "K44") (pin "3") (pinfunction "CA_3") (pintype "passive"))
      (node (ref "X30") (pin "17") (pinfunction "17_17") (pintype "passive"))
    )
    (net (code "165") (name "Net-(K44A-CB)") (class "Default")
      (node (ref "K44") (pin "4") (pinfunction "CB_4") (pintype "passive"))
      (node (ref "X28") (pin "17") (pinfunction "17_17") (pintype "passive"))
    )
    (net (code "166") (name "Net-(K44B--)") (class "Default")
      (node (ref "K44") (pin "2") (pinfunction "-_2") (pintype "passive"))
      (node (ref "Q27") (pin "3") (pinfunction "D_3") (pintype "passive"))
    )
    (net (code "167") (name "Net-(K45A-CA)") (class "Default")
      (node (ref "K45") (pin "3") (pinfunction "CA_3") (pintype "passive"))
      (node (ref "X30") (pin "18") (pinfunction "18_18") (pintype "passive"))
    )
    (net (code "168") (name "Net-(K45A-CB)") (class "Default")
      (node (ref "K45") (pin "4") (pinfunction "CB_4") (pintype "passive"))
      (node (ref "X28") (pin "18") (pinfunction "18_18") (pintype "passive"))
    )
    (net (code "169") (name "Net-(K45B--)") (class "Default")
      (node (ref "K45") (pin "2") (pinfunction "-_2") (pintype "passive"))
      (node (ref "Q46") (pin "3") (pinfunction "D_3") (pintype "passive"))
    )
    (net (code "170") (name "Net-(K46A-CA)") (class "Default")
      (node (ref "K46") (pin "3") (pinfunction "CA_3") (pintype "passive"))
      (node (ref "X30") (pin "19") (pinfunction "19_19") (pintype "passive"))
    )
    (net (code "171") (name "Net-(K46A-CB)") (class "Default")
      (node (ref "K46") (pin "4") (pinfunction "CB_4") (pintype "passive"))
      (node (ref "X28") (pin "19") (pinfunction "19_19") (pintype "passive"))
    )
    (net (code "172") (name "Net-(K46B--)") (class "Default")
      (node (ref "K46") (pin "2") (pinfunction "-_2") (pintype "passive"))
      (node (ref "Q47") (pin "3") (pinfunction "D_3") (pintype "passive"))
    )
    (net (code "173") (name "Net-(K47A-CA)") (class "Default")
      (node (ref "K47") (pin "3") (pinfunction "CA_3") (pintype "passive"))
      (node (ref "X30") (pin "20") (pinfunction "20_20") (pintype "passive"))
    )
    (net (code "174") (name "Net-(K47A-CB)") (class "Default")
      (node (ref "K47") (pin "4") (pinfunction "CB_4") (pintype "passive"))
      (node (ref "X28") (pin "20") (pinfunction "20_20") (pintype "passive"))
    )
    (net (code "175") (name "Net-(K47B--)") (class "Default")
      (node (ref "K47") (pin "2") (pinfunction "-_2") (pintype "passive"))
      (node (ref "Q48") (pin "3") (pinfunction "D_3") (pintype "passive"))
    )
    (net (code "176") (name "Net-(K48A-CA)") (class "Default")
      (node (ref "K48") (pin "3") (pinfunction "CA_3") (pintype "passive"))
      (node (ref "X30") (pin "21") (pinfunction "21_21") (pintype "passive"))
    )
    (net (code "177") (name "Net-(K48A-CB)") (class "Default")
      (node (ref "K48") (pin "4") (pinfunction "CB_4") (pintype "passive"))
      (node (ref "X28") (pin "21") (pinfunction "21_21") (pintype "passive"))
    )
    (net (code "178") (name "Net-(K48B--)") (class "Default")
      (node (ref "K48") (pin "2") (pinfunction "-_2") (pintype "passive"))
      (node (ref "Q49") (pin "3") (pinfunction "D_3") (pintype "passive"))
    )
    (net (code "179") (name "Net-(K49A-CA)") (class "Default")
      (node (ref "K49") (pin "3") (pinfunction "CA_3") (pintype "passive"))
      (node (ref "X30") (pin "22") (pinfunction "22_22") (pintype "passive"))
    )
    (net (code "180") (name "Net-(K49A-CB)") (class "Default")
      (node (ref "K49") (pin "4") (pinfunction "CB_4") (pintype "passive"))
      (node (ref "X28") (pin "22") (pinfunction "22_22") (pintype "passive"))
    )
    (net (code "181") (name "Net-(K49B--)") (class "Default")
      (node (ref "K49") (pin "2") (pinfunction "-_2") (pintype "passive"))
      (node (ref "Q50") (pin "3") (pinfunction "D_3") (pintype "passive"))
    )
    (net (code "182") (name "Net-(K50A-CA)") (class "Default")
      (node (ref "K50") (pin "3") (pinfunction "CA_3") (pintype "passive"))
      (node (ref "X30") (pin "23") (pinfunction "23_23") (pintype "passive"))
    )
    (net (code "183") (name "Net-(K50A-CB)") (class "Default")
      (node (ref "K50") (pin "4") (pinfunction "CB_4") (pintype "passive"))
      (node (ref "X28") (pin "23") (pinfunction "23_23") (pintype "passive"))
    )
    (net (code "184") (name "Net-(K50B--)") (class "Default")
      (node (ref "K50") (pin "2") (pinfunction "-_2") (pintype "passive"))
      (node (ref "Q51") (pin "3") (pinfunction "D_3") (pintype "passive"))
    )
    (net (code "185") (name "Net-(K51A-CA)") (class "Default")
      (node (ref "K51") (pin "3") (pinfunction "CA_3") (pintype "passive"))
      (node (ref "X30") (pin "24") (pinfunction "24_24") (pintype "passive"))
    )
    (net (code "186") (name "Net-(K51A-CB)") (class "Default")
      (node (ref "K51") (pin "4") (pinfunction "CB_4") (pintype "passive"))
      (node (ref "X28") (pin "24") (pinfunction "24_24") (pintype "passive"))
    )
    (net (code "187") (name "Net-(K51B--)") (class "Default")
      (node (ref "K51") (pin "2") (pinfunction "-_2") (pintype "passive"))
      (node (ref "Q52") (pin "3") (pinfunction "D_3") (pintype "passive"))
    )
    (net (code "188") (name "Net-(K52A-CA)") (class "Default")
      (node (ref "K52") (pin "3") (pinfunction "CA_3") (pintype "passive"))
      (node (ref "X30") (pin "25") (pinfunction "25_25") (pintype "passive"))
    )
    (net (code "189") (name "Net-(K52A-CB)") (class "Default")
      (node (ref "K52") (pin "4") (pinfunction "CB_4") (pintype "passive"))
      (node (ref "X28") (pin "25") (pinfunction "25_25") (pintype "passive"))
    )
    (net (code "190") (name "Net-(K52B--)") (class "Default")
      (node (ref "K52") (pin "2") (pinfunction "-_2") (pintype "passive"))
      (node (ref "Q53") (pin "3") (pinfunction "D_3") (pintype "passive"))
    )
    (net (code "191") (name "Net-(K53A-CA)") (class "Default")
      (node (ref "K53") (pin "3") (pinfunction "CA_3") (pintype "passive"))
      (node (ref "X30") (pin "26") (pinfunction "26_26") (pintype "passive"))
    )
    (net (code "192") (name "Net-(K53A-CB)") (class "Default")
      (node (ref "K53") (pin "4") (pinfunction "CB_4") (pintype "passive"))
      (node (ref "X28") (pin "26") (pinfunction "26_26") (pintype "passive"))
    )
    (net (code "193") (name "Net-(K53B--)") (class "Default")
      (node (ref "K53") (pin "2") (pinfunction "-_2") (pintype "passive"))
      (node (ref "Q54") (pin "3") (pinfunction "D_3") (pintype "passive"))
    )
    (net (code "194") (name "Net-(K54A-CA)") (class "Default")
      (node (ref "K54") (pin "3") (pinfunction "CA_3") (pintype "passive"))
      (node (ref "X30") (pin "27") (pinfunction "27_27") (pintype "passive"))
    )
    (net (code "195") (name "Net-(K54A-CB)") (class "Default")
      (node (ref "K54") (pin "4") (pinfunction "CB_4") (pintype "passive"))
      (node (ref "X28") (pin "27") (pinfunction "27_27") (pintype "passive"))
    )
    (net (code "196") (name "Net-(K54B--)") (class "Default")
      (node (ref "K54") (pin "2") (pinfunction "-_2") (pintype "passive"))
      (node (ref "Q55") (pin "3") (pinfunction "D_3") (pintype "passive"))
    )
    (net (code "197") (name "Net-(K55A-CA)") (class "Default")
      (node (ref "K55") (pin "3") (pinfunction "CA_3") (pintype "passive"))
      (node (ref "X30") (pin "28") (pinfunction "28_28") (pintype "passive"))
    )
    (net (code "198") (name "Net-(K55A-CB)") (class "Default")
      (node (ref "K55") (pin "4") (pinfunction "CB_4") (pintype "passive"))
      (node (ref "X28") (pin "28") (pinfunction "28_28") (pintype "passive"))
    )
    (net (code "199") (name "Net-(K55B--)") (class "Default")
      (node (ref "K55") (pin "2") (pinfunction "-_2") (pintype "passive"))
      (node (ref "Q56") (pin "3") (pinfunction "D_3") (pintype "passive"))
    )
    (net (code "200") (name "Net-(K56A-CA)") (class "Default")
      (node (ref "K56") (pin "3") (pinfunction "CA_3") (pintype "passive"))
      (node (ref "X30") (pin "29") (pinfunction "29_29") (pintype "passive"))
    )
    (net (code "201") (name "Net-(K56A-CB)") (class "Default")
      (node (ref "K56") (pin "4") (pinfunction "CB_4") (pintype "passive"))
      (node (ref "X28") (pin "29") (pinfunction "29_29") (pintype "passive"))
    )
    (net (code "202") (name "Net-(K56B--)") (class "Default")
      (node (ref "K56") (pin "2") (pinfunction "-_2") (pintype "passive"))
      (node (ref "Q57") (pin "3") (pinfunction "D_3") (pintype "passive"))
    )
    (net (code "203") (name "Net-(K57A-CA)") (class "Default")
      (node (ref "K57") (pin "3") (pinfunction "CA_3") (pintype "passive"))
      (node (ref "X30") (pin "30") (pinfunction "30_30") (pintype "passive"))
    )
    (net (code "204") (name "Net-(K57A-CB)") (class "Default")
      (node (ref "K57") (pin "4") (pinfunction "CB_4") (pintype "passive"))
      (node (ref "X28") (pin "30") (pinfunction "30_30") (pintype "passive"))
    )
    (net (code "205") (name "Net-(K57B--)") (class "Default")
      (node (ref "K57") (pin "2") (pinfunction "-_2") (pintype "passive"))
      (node (ref "Q58") (pin "3") (pinfunction "D_3") (pintype "passive"))
    )
    (net (code "206") (name "Net-(K58A-CA)") (class "Default")
      (node (ref "K58") (pin "3") (pinfunction "CA_3") (pintype "passive"))
      (node (ref "X30") (pin "31") (pinfunction "31_31") (pintype "passive"))
    )
    (net (code "207") (name "Net-(K58A-CB)") (class "Default")
      (node (ref "K58") (pin "4") (pinfunction "CB_4") (pintype "passive"))
      (node (ref "X28") (pin "31") (pinfunction "31_31") (pintype "passive"))
    )
    (net (code "208") (name "Net-(K58B--)") (class "Default")
      (node (ref "K58") (pin "2") (pinfunction "-_2") (pintype "passive"))
      (node (ref "Q59") (pin "3") (pinfunction "D_3") (pintype "passive"))
    )
    (net (code "209") (name "Net-(K59A-CA)") (class "Default")
      (node (ref "K59") (pin "3") (pinfunction "CA_3") (pintype "passive"))
      (node (ref "X30") (pin "32") (pinfunction "32_32") (pintype "passive"))
    )
    (net (code "210") (name "Net-(K59A-CB)") (class "Default")
      (node (ref "K59") (pin "4") (pinfunction "CB_4") (pintype "passive"))
      (node (ref "X28") (pin "32") (pinfunction "32_32") (pintype "passive"))
    )
    (net (code "211") (name "Net-(K59B--)") (class "Default")
      (node (ref "K59") (pin "2") (pinfunction "-_2") (pintype "passive"))
      (node (ref "Q60") (pin "3") (pinfunction "D_3") (pintype "passive"))
    )
    (net (code "212") (name "Net-(K60A-CA)") (class "Default")
      (node (ref "K60") (pin "3") (pinfunction "CA_3") (pintype "passive"))
      (node (ref "X30") (pin "33") (pinfunction "33_33") (pintype "passive"))
    )
    (net (code "213") (name "Net-(K60A-CB)") (class "Default")
      (node (ref "K60") (pin "4") (pinfunction "CB_4") (pintype "passive"))
      (node (ref "X28") (pin "33") (pinfunction "33_33") (pintype "passive"))
    )
    (net (code "214") (name "Net-(K60B--)") (class "Default")
      (node (ref "K60") (pin "2") (pinfunction "-_2") (pintype "passive"))
      (node (ref "Q61") (pin "3") (pinfunction "D_3") (pintype "passive"))
    )
    (net (code "215") (name "Net-(K61A-CA)") (class "Default")
      (node (ref "K61") (pin "3") (pinfunction "CA_3") (pintype "passive"))
      (node (ref "X30") (pin "34") (pinfunction "34_34") (pintype "passive"))
    )
    (net (code "216") (name "Net-(K61A-CB)") (class "Default")
      (node (ref "K61") (pin "4") (pinfunction "CB_4") (pintype "passive"))
      (node (ref "X28") (pin "34") (pinfunction "34_34") (pintype "passive"))
    )
    (net (code "217") (name "Net-(K61B--)") (class "Default")
      (node (ref "K61") (pin "2") (pinfunction "-_2") (pintype "passive"))
      (node (ref "Q62") (pin "3") (pinfunction "D_3") (pintype "passive"))
    )
    (net (code "218") (name "Net-(K62A-CA)") (class "Default")
      (node (ref "K62") (pin "3") (pinfunction "CA_3") (pintype "passive"))
      (node (ref "X30") (pin "35") (pinfunction "35_35") (pintype "passive"))
    )
    (net (code "219") (name "Net-(K62A-CB)") (class "Default")
      (node (ref "K62") (pin "4") (pinfunction "CB_4") (pintype "passive"))
      (node (ref "X28") (pin "35") (pinfunction "35_35") (pintype "passive"))
    )
    (net (code "220") (name "Net-(K62B--)") (class "Default")
      (node (ref "K62") (pin "2") (pinfunction "-_2") (pintype "passive"))
      (node (ref "Q63") (pin "3") (pinfunction "D_3") (pintype "passive"))
    )
    (net (code "221") (name "Net-(K63A-CA)") (class "Default")
      (node (ref "K63") (pin "3") (pinfunction "CA_3") (pintype "passive"))
      (node (ref "X30") (pin "36") (pinfunction "36_36") (pintype "passive"))
    )
    (net (code "222") (name "Net-(K63A-CB)") (class "Default")
      (node (ref "K63") (pin "4") (pinfunction "CB_4") (pintype "passive"))
      (node (ref "X28") (pin "36") (pinfunction "36_36") (pintype "passive"))
    )
    (net (code "223") (name "Net-(K63B--)") (class "Default")
      (node (ref "K63") (pin "2") (pinfunction "-_2") (pintype "passive"))
      (node (ref "Q64") (pin "3") (pinfunction "D_3") (pintype "passive"))
    )
    (net (code "224") (name "Net-(K64A-CA)") (class "Default")
      (node (ref "K64") (pin "3") (pinfunction "CA_3") (pintype "passive"))
      (node (ref "X30") (pin "37") (pinfunction "37_37") (pintype "passive"))
    )
    (net (code "225") (name "Net-(K64A-CB)") (class "Default")
      (node (ref "K64") (pin "4") (pinfunction "CB_4") (pintype "passive"))
      (node (ref "X28") (pin "37") (pinfunction "37_37") (pintype "passive"))
    )
    (net (code "226") (name "Net-(K64B--)") (class "Default")
      (node (ref "K64") (pin "2") (pinfunction "-_2") (pintype "passive"))
      (node (ref "Q65") (pin "3") (pinfunction "D_3") (pintype "passive"))
    )
    (net (code "227") (name "Net-(K65A-CA)") (class "Default")
      (node (ref "K65") (pin "3") (pinfunction "CA_3") (pintype "passive"))
      (node (ref "X30") (pin "38") (pinfunction "38_38") (pintype "passive"))
    )
    (net (code "228") (name "Net-(K65A-CB)") (class "Default")
      (node (ref "K65") (pin "4") (pinfunction "CB_4") (pintype "passive"))
      (node (ref "X28") (pin "38") (pinfunction "38_38") (pintype "passive"))
    )
    (net (code "229") (name "Net-(K65B--)") (class "Default")
      (node (ref "K65") (pin "2") (pinfunction "-_2") (pintype "passive"))
      (node (ref "Q66") (pin "3") (pinfunction "D_3") (pintype "passive"))
    )
    (net (code "230") (name "Net-(K66A-CA)") (class "Default")
      (node (ref "K66") (pin "3") (pinfunction "CA_3") (pintype "passive"))
      (node (ref "X30") (pin "39") (pinfunction "39_39") (pintype "passive"))
    )
    (net (code "231") (name "Net-(K66A-CB)") (class "Default")
      (node (ref "K66") (pin "4") (pinfunction "CB_4") (pintype "passive"))
      (node (ref "X28") (pin "39") (pinfunction "39_39") (pintype "passive"))
    )
    (net (code "232") (name "Net-(K66B--)") (class "Default")
      (node (ref "K66") (pin "2") (pinfunction "-_2") (pintype "passive"))
      (node (ref "Q67") (pin "3") (pinfunction "D_3") (pintype "passive"))
    )
    (net (code "233") (name "Net-(K67A-CA)") (class "Default")
      (node (ref "K67") (pin "3") (pinfunction "CA_3") (pintype "passive"))
      (node (ref "X30") (pin "40") (pinfunction "40_40") (pintype "passive"))
    )
    (net (code "234") (name "Net-(K67A-CB)") (class "Default")
      (node (ref "K67") (pin "4") (pinfunction "CB_4") (pintype "passive"))
      (node (ref "X28") (pin "40") (pinfunction "40_40") (pintype "passive"))
    )
    (net (code "235") (name "Net-(K67B--)") (class "Default")
      (node (ref "K67") (pin "2") (pinfunction "-_2") (pintype "passive"))
      (node (ref "Q68") (pin "3") (pinfunction "D_3") (pintype "passive"))
    )
    (net (code "236") (name "Net-(K68A-CA)") (class "Default")
      (node (ref "K68") (pin "3") (pinfunction "CA_3") (pintype "passive"))
      (node (ref "X30") (pin "41") (pinfunction "41_41") (pintype "passive"))
    )
    (net (code "237") (name "Net-(K68A-CB)") (class "Default")
      (node (ref "K68") (pin "4") (pinfunction "CB_4") (pintype "passive"))
      (node (ref "X28") (pin "41") (pinfunction "41_41") (pintype "passive"))
    )
    (net (code "238") (name "Net-(K68B--)") (class "Default")
      (node (ref "K68") (pin "2") (pinfunction "-_2") (pintype "passive"))
      (node (ref "Q69") (pin "3") (pinfunction "D_3") (pintype "passive"))
    )
    (net (code "239") (name "Net-(K69A-CA)") (class "Default")
      (node (ref "K69") (pin "3") (pinfunction "CA_3") (pintype "passive"))
      (node (ref "X30") (pin "42") (pinfunction "42_42") (pintype "passive"))
    )
    (net (code "240") (name "Net-(K69A-CB)") (class "Default")
      (node (ref "K69") (pin "4") (pinfunction "CB_4") (pintype "passive"))
      (node (ref "X28") (pin "42") (pinfunction "42_42") (pintype "passive"))
    )
    (net (code "241") (name "Net-(K69B--)") (class "Default")
      (node (ref "K69") (pin "2") (pinfunction "-_2") (pintype "passive"))
      (node (ref "Q70") (pin "3") (pinfunction "D_3") (pintype "passive"))
    )
    (net (code "242") (name "Net-(K70A-CA)") (class "Default")
      (node (ref "K70") (pin "3") (pinfunction "CA_3") (pintype "passive"))
      (node (ref "X30") (pin "43") (pinfunction "43_43") (pintype "passive"))
    )
    (net (code "243") (name "Net-(K70A-CB)") (class "Default")
      (node (ref "K70") (pin "4") (pinfunction "CB_4") (pintype "passive"))
      (node (ref "X28") (pin "43") (pinfunction "43_43") (pintype "passive"))
    )
    (net (code "244") (name "Net-(K70B--)") (class "Default")
      (node (ref "K70") (pin "2") (pinfunction "-_2") (pintype "passive"))
      (node (ref "Q71") (pin "3") (pinfunction "D_3") (pintype "passive"))
    )
    (net (code "245") (name "Net-(K71A-CA)") (class "Default")
      (node (ref "K71") (pin "3") (pinfunction "CA_3") (pintype "passive"))
      (node (ref "X30") (pin "44") (pinfunction "44_44") (pintype "passive"))
    )
    (net (code "246") (name "Net-(K71A-CB)") (class "Default")
      (node (ref "K71") (pin "4") (pinfunction "CB_4") (pintype "passive"))
      (node (ref "X28") (pin "44") (pinfunction "44_44") (pintype "passive"))
    )
    (net (code "247") (name "Net-(K71B--)") (class "Default")
      (node (ref "K71") (pin "2") (pinfunction "-_2") (pintype "passive"))
      (node (ref "Q72") (pin "3") (pinfunction "D_3") (pintype "passive"))
    )
    (net (code "248") (name "Net-(K72A-CA)") (class "Default")
      (node (ref "K72") (pin "3") (pinfunction "CA_3") (pintype "passive"))
      (node (ref "X30") (pin "45") (pinfunction "45_45") (pintype "passive"))
    )
    (net (code "249") (name "Net-(K72A-CB)") (class "Default")
      (node (ref "K72") (pin "4") (pinfunction "CB_4") (pintype "passive"))
      (node (ref "X28") (pin "45") (pinfunction "45_45") (pintype "passive"))
    )
    (net (code "250") (name "Net-(K72B--)") (class "Default")
      (node (ref "K72") (pin "2") (pinfunction "-_2") (pintype "passive"))
      (node (ref "Q73") (pin "3") (pinfunction "D_3") (pintype "passive"))
    )
    (net (code "251") (name "Net-(K73A-CA)") (class "Default")
      (node (ref "K73") (pin "3") (pinfunction "CA_3") (pintype "passive"))
      (node (ref "X30") (pin "46") (pinfunction "46_46") (pintype "passive"))
    )
    (net (code "252") (name "Net-(K73A-CB)") (class "Default")
      (node (ref "K73") (pin "4") (pinfunction "CB_4") (pintype "passive"))
      (node (ref "X28") (pin "46") (pinfunction "46_46") (pintype "passive"))
    )
    (net (code "253") (name "Net-(K73B--)") (class "Default")
      (node (ref "K73") (pin "2") (pinfunction "-_2") (pintype "passive"))
      (node (ref "Q74") (pin "3") (pinfunction "D_3") (pintype "passive"))
    )
    (net (code "254") (name "Net-(K74A-CA)") (class "Default")
      (node (ref "K74") (pin "3") (pinfunction "CA_3") (pintype "passive"))
      (node (ref "X30") (pin "47") (pinfunction "47_47") (pintype "passive"))
    )
    (net (code "255") (name "Net-(K74A-CB)") (class "Default")
      (node (ref "K74") (pin "4") (pinfunction "CB_4") (pintype "passive"))
      (node (ref "X28") (pin "47") (pinfunction "47_47") (pintype "passive"))
    )
    (net (code "256") (name "Net-(K74B--)") (class "Default")
      (node (ref "K74") (pin "2") (pinfunction "-_2") (pintype "passive"))
      (node (ref "Q75") (pin "3") (pinfunction "D_3") (pintype "passive"))
    )
    (net (code "257") (name "Net-(K75A-CA)") (class "Default")
      (node (ref "K75") (pin "3") (pinfunction "CA_3") (pintype "passive"))
      (node (ref "X30") (pin "48") (pinfunction "48_48") (pintype "passive"))
    )
    (net (code "258") (name "Net-(K75A-CB)") (class "Default")
      (node (ref "K75") (pin "4") (pinfunction "CB_4") (pintype "passive"))
      (node (ref "X28") (pin "48") (pinfunction "48_48") (pintype "passive"))
    )
    (net (code "259") (name "Net-(K75B--)") (class "Default")
      (node (ref "K75") (pin "2") (pinfunction "-_2") (pintype "passive"))
      (node (ref "Q76") (pin "3") (pinfunction "D_3") (pintype "passive"))
    )
    (net (code "260") (name "Net-(K76A-CA)") (class "Default")
      (node (ref "K76") (pin "3") (pinfunction "CA_3") (pintype "passive"))
      (node (ref "X30") (pin "49") (pinfunction "49_49") (pintype "passive"))
    )
    (net (code "261") (name "Net-(K76A-CB)") (class "Default")
      (node (ref "K76") (pin "4") (pinfunction "CB_4") (pintype "passive"))
      (node (ref "X28") (pin "49") (pinfunction "49_49") (pintype "passive"))
    )
    (net (code "262") (name "Net-(K76B--)") (class "Default")
      (node (ref "K76") (pin "2") (pinfunction "-_2") (pintype "passive"))
      (node (ref "Q81") (pin "3") (pinfunction "D_3") (pintype "passive"))
    )
    (net (code "263") (name "Net-(K77A-CA)") (class "Default")
      (node (ref "K77") (pin "3") (pinfunction "CA_3") (pintype "passive"))
      (node (ref "X30") (pin "50") (pinfunction "50_50") (pintype "passive"))
    )
    (net (code "264") (name "Net-(K77A-CB)") (class "Default")
      (node (ref "K77") (pin "4") (pinfunction "CB_4") (pintype "passive"))
      (node (ref "X28") (pin "50") (pinfunction "50_50") (pintype "passive"))
    )
    (net (code "265") (name "Net-(K77B--)") (class "Default")
      (node (ref "K77") (pin "2") (pinfunction "-_2") (pintype "passive"))
      (node (ref "Q82") (pin "3") (pinfunction "D_3") (pintype "passive"))
    )
    (net (code "266") (name "Net-(K78A-CA)") (class "Default")
      (node (ref "K78") (pin "3") (pinfunction "CA_3") (pintype "passive"))
      (node (ref "X30") (pin "51") (pinfunction "51_51") (pintype "passive"))
    )
    (net (code "267") (name "Net-(K78A-CB)") (class "Default")
      (node (ref "K78") (pin "4") (pinfunction "CB_4") (pintype "passive"))
      (node (ref "X28") (pin "51") (pinfunction "51_51") (pintype "passive"))
    )
    (net (code "268") (name "Net-(K78B--)") (class "Default")
      (node (ref "K78") (pin "2") (pinfunction "-_2") (pintype "passive"))
      (node (ref "Q83") (pin "3") (pinfunction "D_3") (pintype "passive"))
    )
    (net (code "269") (name "Net-(K79A-CA)") (class "Default")
      (node (ref "K79") (pin "3") (pinfunction "CA_3") (pintype "passive"))
      (node (ref "X30") (pin "52") (pinfunction "52_52") (pintype "passive"))
    )
    (net (code "270") (name "Net-(K79A-CB)") (class "Default")
      (node (ref "K79") (pin "4") (pinfunction "CB_4") (pintype "passive"))
      (node (ref "X28") (pin "52") (pinfunction "52_52") (pintype "passive"))
    )
    (net (code "271") (name "Net-(K79B--)") (class "Default")
      (node (ref "K79") (pin "2") (pinfunction "-_2") (pintype "passive"))
      (node (ref "Q84") (pin "3") (pinfunction "D_3") (pintype "passive"))
    )
    (net (code "272") (name "Net-(K80A-CA)") (class "Default")
      (node (ref "K80") (pin "3") (pinfunction "CA_3") (pintype "passive"))
      (node (ref "X30") (pin "53") (pinfunction "53_53") (pintype "passive"))
    )
    (net (code "273") (name "Net-(K80A-CB)") (class "Default")
      (node (ref "K80") (pin "4") (pinfunction "CB_4") (pintype "passive"))
      (node (ref "X28") (pin "53") (pinfunction "53_53") (pintype "passive"))
    )
    (net (code "274") (name "Net-(K80B--)") (class "Default")
      (node (ref "K80") (pin "2") (pinfunction "-_2") (pintype "passive"))
      (node (ref "Q85") (pin "3") (pinfunction "D_3") (pintype "passive"))
    )
    (net (code "275") (name "Net-(K81A-CA)") (class "Default")
      (node (ref "K81") (pin "3") (pinfunction "CA_3") (pintype "passive"))
      (node (ref "X30") (pin "54") (pinfunction "54_54") (pintype "passive"))
    )
    (net (code "276") (name "Net-(K81A-CB)") (class "Default")
      (node (ref "K81") (pin "4") (pinfunction "CB_4") (pintype "passive"))
      (node (ref "X28") (pin "54") (pinfunction "54_54") (pintype "passive"))
    )
    (net (code "277") (name "Net-(K81B--)") (class "Default")
      (node (ref "K81") (pin "2") (pinfunction "-_2") (pintype "passive"))
      (node (ref "Q86") (pin "3") (pinfunction "D_3") (pintype "passive"))
    )
    (net (code "278") (name "Net-(K82A-CA)") (class "Default")
      (node (ref "K82") (pin "3") (pinfunction "CA_3") (pintype "passive"))
      (node (ref "X30") (pin "55") (pinfunction "55_55") (pintype "passive"))
    )
    (net (code "279") (name "Net-(K82A-CB)") (class "Default")
      (node (ref "K82") (pin "4") (pinfunction "CB_4") (pintype "passive"))
      (node (ref "X28") (pin "55") (pinfunction "55_55") (pintype "passive"))
    )
    (net (code "280") (name "Net-(K82B--)") (class "Default")
      (node (ref "K82") (pin "2") (pinfunction "-_2") (pintype "passive"))
      (node (ref "Q87") (pin "3") (pinfunction "D_3") (pintype "passive"))
    )
    (net (code "281") (name "Net-(K83A-CA)") (class "Default")
      (node (ref "K83") (pin "3") (pinfunction "CA_3") (pintype "passive"))
      (node (ref "X30") (pin "56") (pinfunction "56_56") (pintype "passive"))
    )
    (net (code "282") (name "Net-(K83A-CB)") (class "Default")
      (node (ref "K83") (pin "4") (pinfunction "CB_4") (pintype "passive"))
      (node (ref "X28") (pin "56") (pinfunction "56_56") (pintype "passive"))
    )
    (net (code "283") (name "Net-(K83B--)") (class "Default")
      (node (ref "K83") (pin "2") (pinfunction "-_2") (pintype "passive"))
      (node (ref "Q88") (pin "3") (pinfunction "D_3") (pintype "passive"))
    )
    (net (code "284") (name "Net-(K84A-CA)") (class "Default")
      (node (ref "K84") (pin "3") (pinfunction "CA_3") (pintype "passive"))
      (node (ref "X30") (pin "57") (pinfunction "57_57") (pintype "passive"))
    )
    (net (code "285") (name "Net-(K84A-CB)") (class "Default")
      (node (ref "K84") (pin "4") (pinfunction "CB_4") (pintype "passive"))
      (node (ref "X28") (pin "57") (pinfunction "57_57") (pintype "passive"))
    )
    (net (code "286") (name "Net-(K84B--)") (class "Default")
      (node (ref "K84") (pin "2") (pinfunction "-_2") (pintype "passive"))
      (node (ref "Q89") (pin "3") (pinfunction "D_3") (pintype "passive"))
    )
    (net (code "287") (name "Net-(K85A-CA)") (class "Default")
      (node (ref "K85") (pin "3") (pinfunction "CA_3") (pintype "passive"))
      (node (ref "X30") (pin "58") (pinfunction "58_58") (pintype "passive"))
    )
    (net (code "288") (name "Net-(K85A-CB)") (class "Default")
      (node (ref "K85") (pin "4") (pinfunction "CB_4") (pintype "passive"))
      (node (ref "X28") (pin "58") (pinfunction "58_58") (pintype "passive"))
    )
    (net (code "289") (name "Net-(K85B--)") (class "Default")
      (node (ref "K85") (pin "2") (pinfunction "-_2") (pintype "passive"))
      (node (ref "Q90") (pin "3") (pinfunction "D_3") (pintype "passive"))
    )
    (net (code "290") (name "Net-(K86A-CA)") (class "Default")
      (node (ref "K86") (pin "3") (pinfunction "CA_3") (pintype "passive"))
      (node (ref "X30") (pin "59") (pinfunction "59_59") (pintype "passive"))
    )
    (net (code "291") (name "Net-(K86A-CB)") (class "Default")
      (node (ref "K86") (pin "4") (pinfunction "CB_4") (pintype "passive"))
      (node (ref "X28") (pin "59") (pinfunction "59_59") (pintype "passive"))
    )
    (net (code "292") (name "Net-(K86B--)") (class "Default")
      (node (ref "K86") (pin "2") (pinfunction "-_2") (pintype "passive"))
      (node (ref "Q91") (pin "3") (pinfunction "D_3") (pintype "passive"))
    )
    (net (code "293") (name "Net-(K87A-CA)") (class "Default")
      (node (ref "K87") (pin "3") (pinfunction "CA_3") (pintype "passive"))
      (node (ref "X30") (pin "60") (pinfunction "60_60") (pintype "passive"))
    )
    (net (code "294") (name "Net-(K87A-CB)") (class "Default")
      (node (ref "K87") (pin "4") (pinfunction "CB_4") (pintype "passive"))
      (node (ref "X28") (pin "60") (pinfunction "60_60") (pintype "passive"))
    )
    (net (code "295") (name "Net-(K87B--)") (class "Default")
      (node (ref "K87") (pin "2") (pinfunction "-_2") (pintype "passive"))
      (node (ref "Q92") (pin "3") (pinfunction "D_3") (pintype "passive"))
    )
    (net (code "296") (name "Net-(K88A-CA)") (class "Default")
      (node (ref "K88") (pin "3") (pinfunction "CA_3") (pintype "passive"))
      (node (ref "X30") (pin "61") (pinfunction "61_61") (pintype "passive"))
    )
    (net (code "297") (name "Net-(K88A-CB)") (class "Default")
      (node (ref "K88") (pin "4") (pinfunction "CB_4") (pintype "passive"))
      (node (ref "X28") (pin "61") (pinfunction "61_61") (pintype "passive"))
    )
    (net (code "298") (name "Net-(K88B--)") (class "Default")
      (node (ref "K88") (pin "2") (pinfunction "-_2") (pintype "passive"))
      (node (ref "Q93") (pin "3") (pinfunction "D_3") (pintype "passive"))
    )
    (net (code "299") (name "Net-(K89A-CA)") (class "Default")
      (node (ref "K89") (pin "3") (pinfunction "CA_3") (pintype "passive"))
      (node (ref "X30") (pin "62") (pinfunction "62_62") (pintype "passive"))
    )
    (net (code "300") (name "Net-(K89A-CB)") (class "Default")
      (node (ref "K89") (pin "4") (pinfunction "CB_4") (pintype "passive"))
      (node (ref "X28") (pin "62") (pinfunction "62_62") (pintype "passive"))
    )
    (net (code "301") (name "Net-(K89B--)") (class "Default")
      (node (ref "K89") (pin "2") (pinfunction "-_2") (pintype "passive"))
      (node (ref "Q94") (pin "3") (pinfunction "D_3") (pintype "passive"))
    )
    (net (code "302") (name "Net-(K90A-CA)") (class "Default")
      (node (ref "K90") (pin "3") (pinfunction "CA_3") (pintype "passive"))
      (node (ref "X30") (pin "63") (pinfunction "63_63") (pintype "passive"))
    )
    (net (code "303") (name "Net-(K90A-CB)") (class "Default")
      (node (ref "K90") (pin "4") (pinfunction "CB_4") (pintype "passive"))
      (node (ref "X28") (pin "63") (pinfunction "63_63") (pintype "passive"))
    )
    (net (code "304") (name "Net-(K90B--)") (class "Default")
      (node (ref "K90") (pin "2") (pinfunction "-_2") (pintype "passive"))
      (node (ref "Q95") (pin "3") (pinfunction "D_3") (pintype "passive"))
    )
    (net (code "305") (name "Net-(K91A-CA)") (class "Default")
      (node (ref "K91") (pin "3") (pinfunction "CA_3") (pintype "passive"))
      (node (ref "X30") (pin "64") (pinfunction "64_64") (pintype "passive"))
    )
    (net (code "306") (name "Net-(K91A-CB)") (class "Default")
      (node (ref "K91") (pin "4") (pinfunction "CB_4") (pintype "passive"))
      (node (ref "X28") (pin "64") (pinfunction "64_64") (pintype "passive"))
    )
    (net (code "307") (name "Net-(K91B--)") (class "Default")
      (node (ref "K91") (pin "2") (pinfunction "-_2") (pintype "passive"))
      (node (ref "Q96") (pin "3") (pinfunction "D_3") (pintype "passive"))
    )
  )
)
